# smarty07.net
KiCad netlist of a schematic drawn in EAGLE
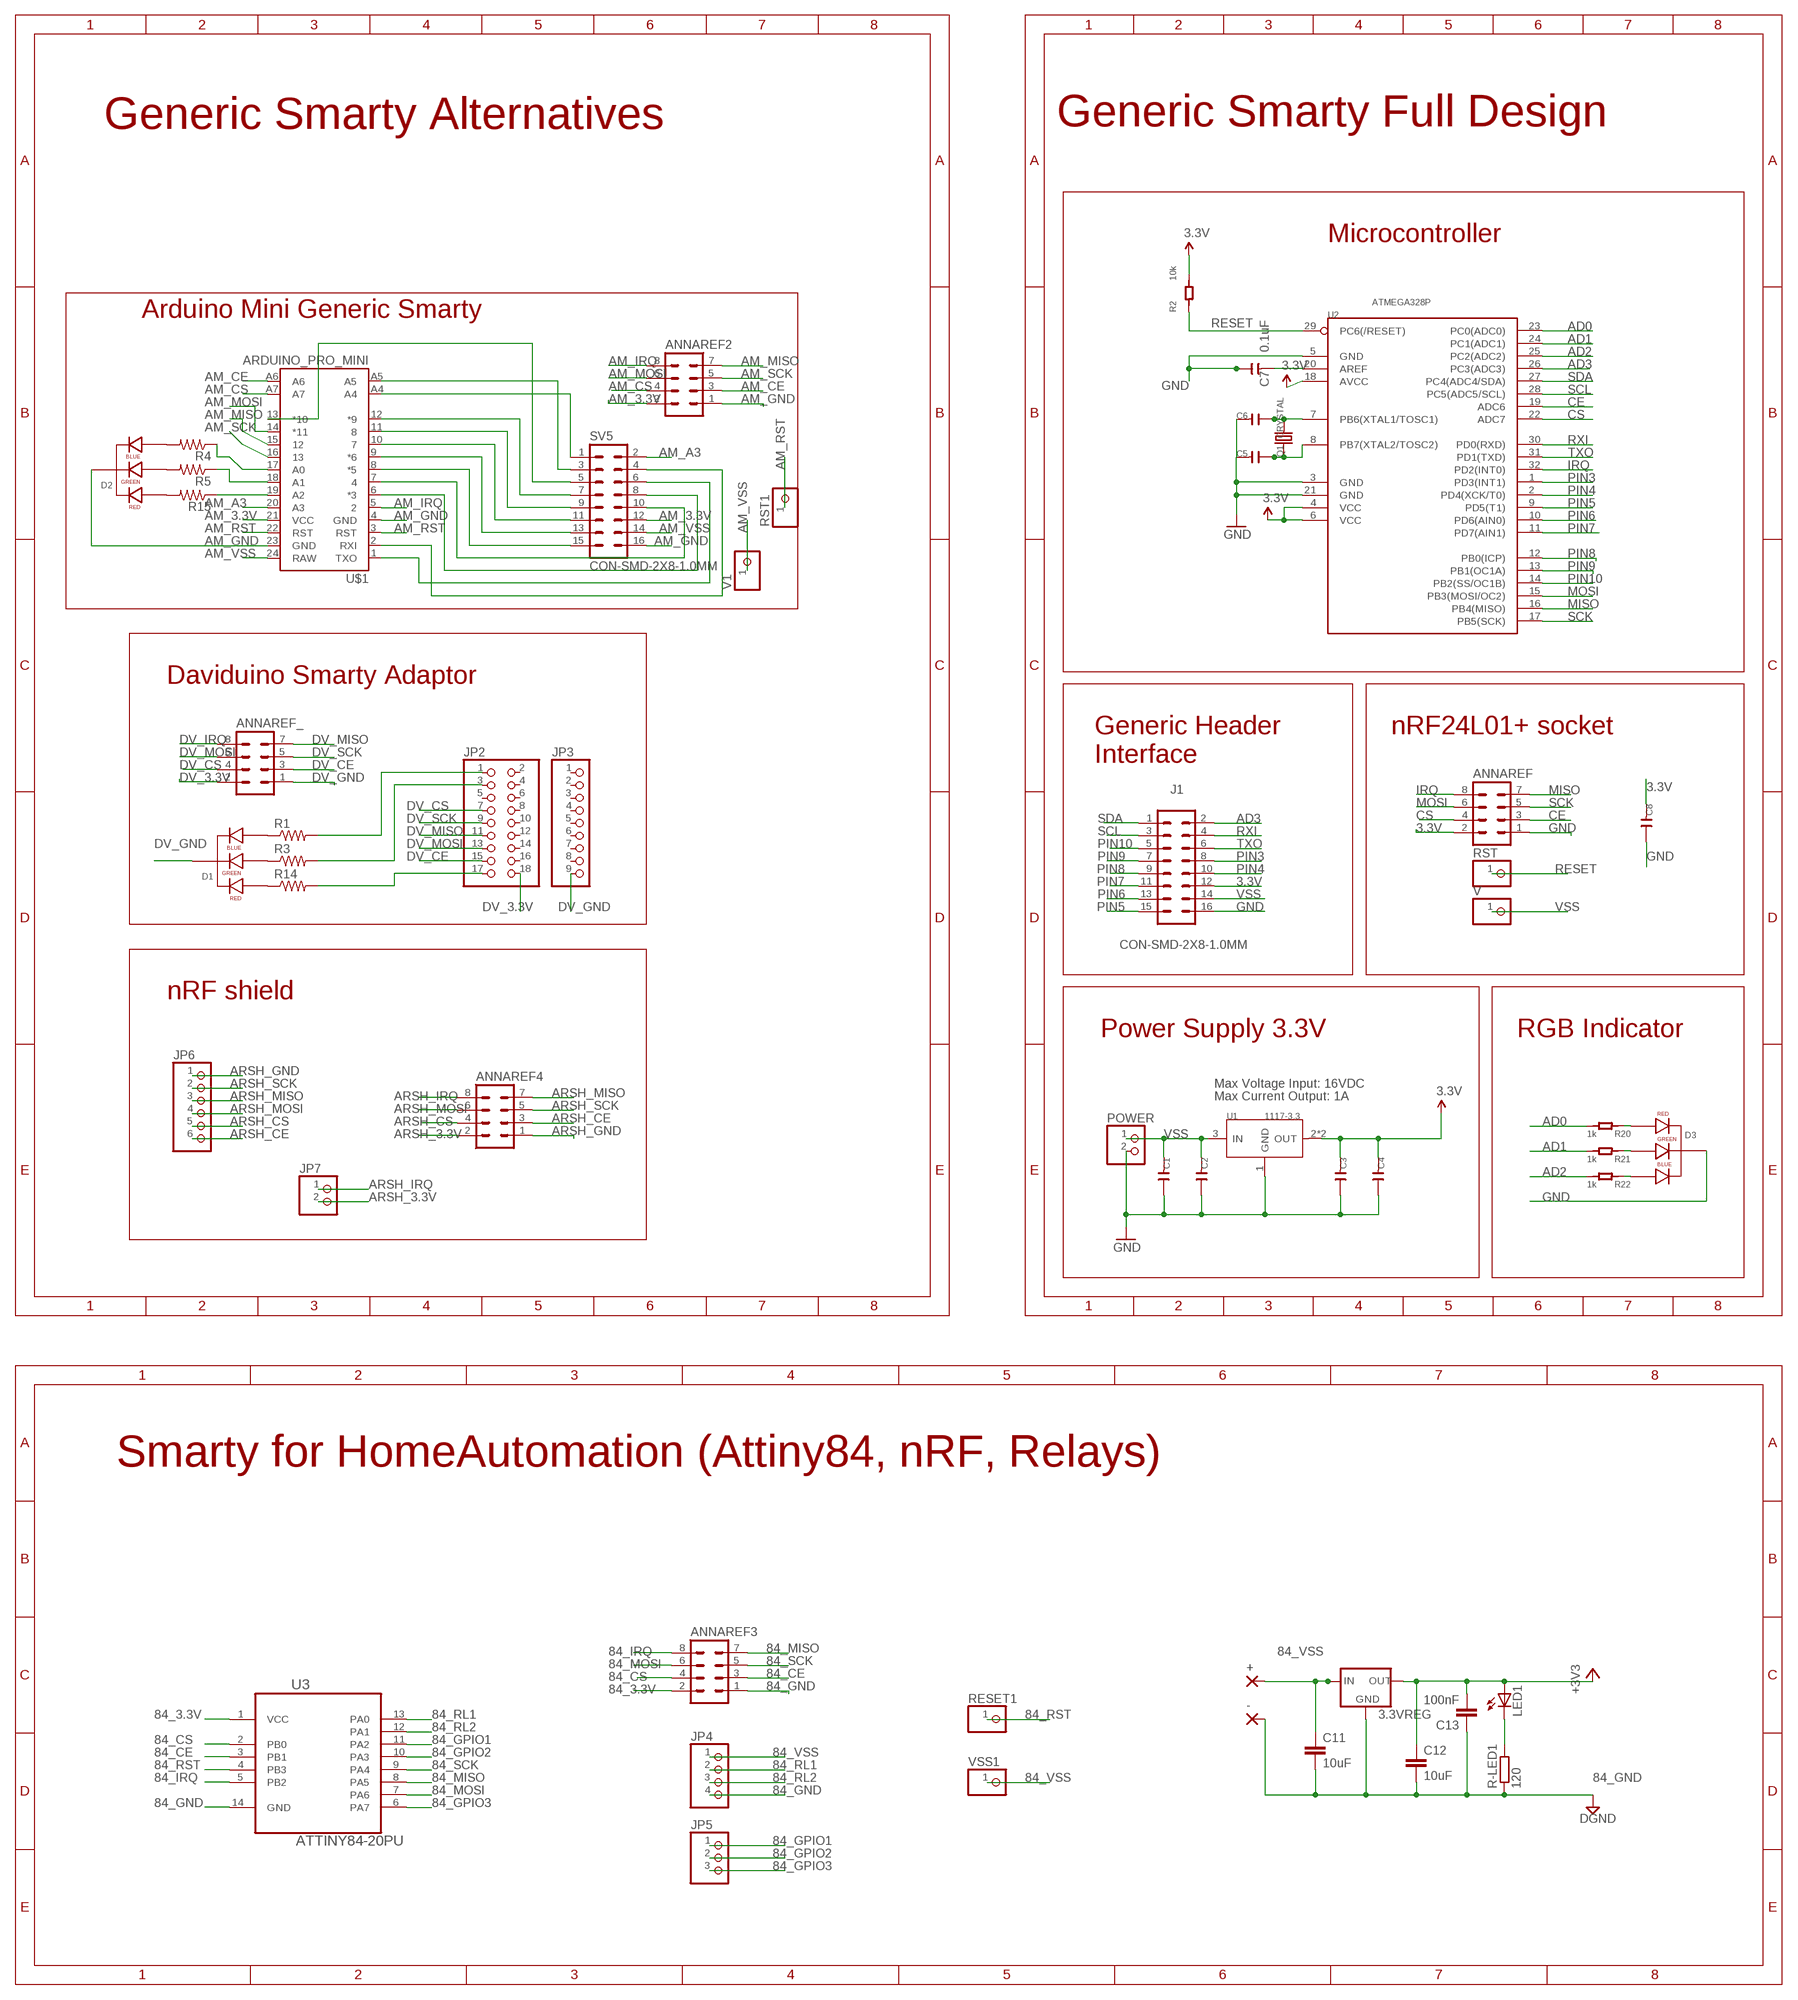
[diagram p0: schematic, sheet 1, part 1 of 2]
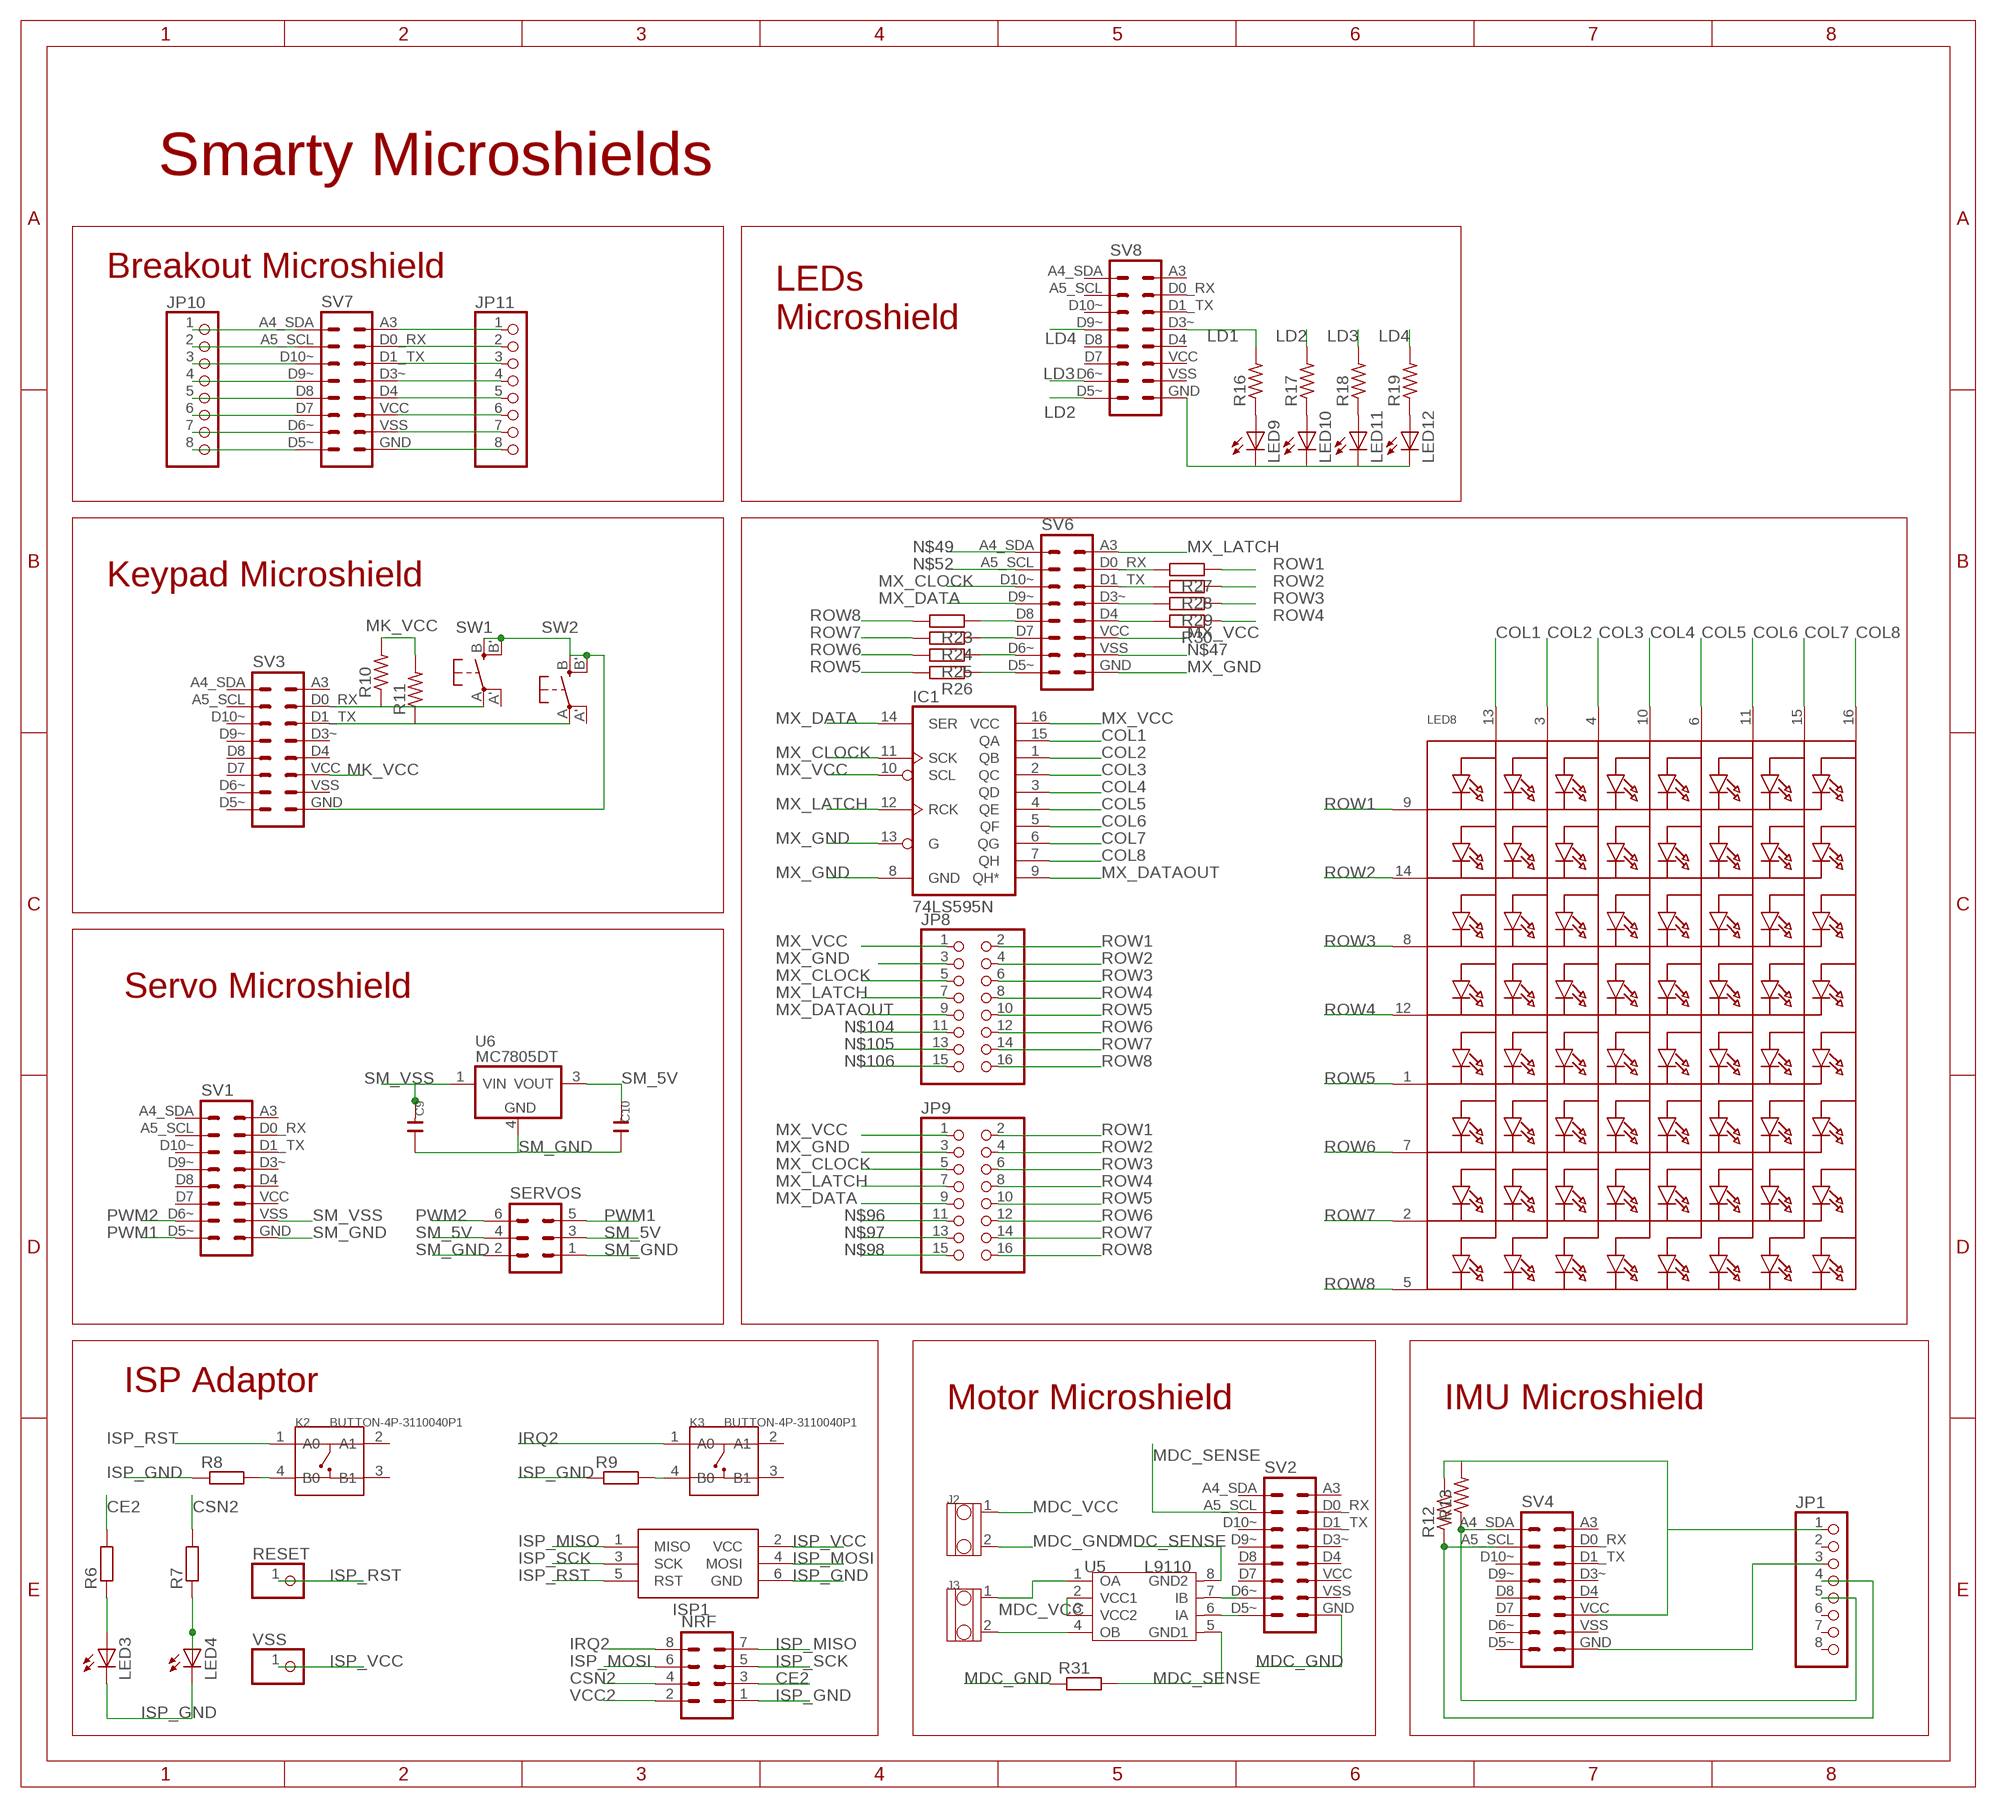
[diagram p1: schematic, sheet 1, part 2 of 2]

(export (version "E")
  (design (tool "Eeschema 10.0.6"))
  (components
    (comp (ref "+")
      (value "2,54/1,1")
      (footprint "eagle-import:2,54_1,1")
      (libsource (lib "eagle-import") (part "2,54/1,1"))
    )
    (comp (ref "-")
      (value "2,54/1,1")
      (footprint "eagle-import:2,54_1,1")
      (libsource (lib "eagle-import") (part "2,54/1,1"))
    )
    (comp (ref "3.3VREG")
      (value "78LXX")
      (footprint "eagle-import:78LXX")
      (libsource (lib "eagle-import") (part "78LXX"))
    )
    (comp (ref "ANNAREF")
      (value "MA04-2")
      (footprint "eagle-import:MA04-2")
      (libsource (lib "eagle-import") (part "MA04-2"))
    )
    (comp (ref "ANNAREF2")
      (value "MA04-2")
      (footprint "eagle-import:MA04-2")
      (libsource (lib "eagle-import") (part "MA04-2"))
    )
    (comp (ref "ANNAREF3")
      (value "MA04-2")
      (footprint "eagle-import:MA04-2")
      (libsource (lib "eagle-import") (part "MA04-2"))
    )
    (comp (ref "ANNAREF4")
      (value "MA04-2")
      (footprint "eagle-import:MA04-2")
      (libsource (lib "eagle-import") (part "MA04-2"))
    )
    (comp (ref "ANNAREF_")
      (value "MA04-2")
      (footprint "eagle-import:MA04-2")
      (libsource (lib "eagle-import") (part "MA04-2"))
    )
    (comp (ref "C1")
      (value "C-0603")
      (footprint "eagle-import:C0603")
      (libsource (lib "eagle-import") (part "C-0603"))
    )
    (comp (ref "C2")
      (value "C-0805")
      (footprint "eagle-import:C0805")
      (libsource (lib "eagle-import") (part "C-0805"))
    )
    (comp (ref "C3")
      (value "C-0603")
      (footprint "eagle-import:C0603")
      (libsource (lib "eagle-import") (part "C-0603"))
    )
    (comp (ref "C4")
      (value "C-0805")
      (footprint "eagle-import:C0805")
      (libsource (lib "eagle-import") (part "C-0805"))
    )
    (comp (ref "C5")
      (value "C-0603")
      (footprint "eagle-import:C0603")
      (libsource (lib "eagle-import") (part "C-0603"))
    )
    (comp (ref "C6")
      (value "C-0603")
      (footprint "eagle-import:C0603")
      (libsource (lib "eagle-import") (part "C-0603"))
    )
    (comp (ref "C7")
      (value "0.1uF")
      (footprint "eagle-import:C0805")
      (libsource (lib "eagle-import") (part "C-0805"))
    )
    (comp (ref "C8")
      (value "C-0805")
      (footprint "eagle-import:C0805")
      (libsource (lib "eagle-import") (part "C-0805"))
    )
    (comp (ref "C9")
      (value "C-0805")
      (footprint "eagle-import:C0805")
      (libsource (lib "eagle-import") (part "C-0805"))
    )
    (comp (ref "C10")
      (value "C-0805")
      (footprint "eagle-import:C0805")
      (libsource (lib "eagle-import") (part "C-0805"))
    )
    (comp (ref "C11")
      (value "10uF")
      (footprint "eagle-import:C025-050X050")
      (libsource (lib "eagle-import") (part "C-EU025-050X050"))
    )
    (comp (ref "C12")
      (value "10uF")
      (footprint "eagle-import:C025-050X050")
      (libsource (lib "eagle-import") (part "C-EU025-050X050"))
    )
    (comp (ref "C13")
      (value "100nF")
      (footprint "eagle-import:C050-024X044")
      (libsource (lib "eagle-import") (part "C-EU050-024X044"))
    )
    (comp (ref "D1")
      (value "LED-RGB-CC-THRUCLEAR")
      (footprint "eagle-import:LED-RGB-THRU")
      (libsource (lib "eagle-import") (part "LED-RGB-CC-THRUCLEAR"))
    )
    (comp (ref "D2")
      (value "LED-RGB-CC-THRUCLEAR")
      (footprint "eagle-import:LED-RGB-THRU")
      (libsource (lib "eagle-import") (part "LED-RGB-CC-THRUCLEAR"))
    )
    (comp (ref "D3")
      (value "LED-RGB-CC-THRUCLEAR")
      (footprint "eagle-import:LED-RGB-THRU")
      (libsource (lib "eagle-import") (part "LED-RGB-CC-THRUCLEAR"))
    )
    (comp (ref "IC1")
      (value "74LS595N")
      (footprint "eagle-import:DIL16")
      (libsource (lib "eagle-import") (part "74595NLS"))
    )
    (comp (ref "ISP1")
      (value "AVRISP-6")
      (footprint "eagle-import:AVRISP")
      (libsource (lib "eagle-import") (part "AVRISP-6"))
    )
    (comp (ref "J1")
      (value "CON-SMD-2X8-1.0MM")
      (footprint "eagle-import:SMRT-FEM-16")
      (libsource (lib "eagle-import") (part "CON-SMD-2X8-1.0MM"))
    )
    (comp (ref "J2")
      (value "SCREW-TERMINAL-2P-3470110P1")
      (footprint "eagle-import:2P-5.0")
      (libsource (lib "eagle-import") (part "SCREW-TERMINAL-2P-3470110P1"))
    )
    (comp (ref "J3")
      (value "SCREW-TERMINAL-2P-3470110P1")
      (footprint "eagle-import:2P-5.0")
      (libsource (lib "eagle-import") (part "SCREW-TERMINAL-2P-3470110P1"))
    )
    (comp (ref "JP1")
      (value "PINHD-1X8BIG")
      (footprint "eagle-import:1X08-BIG")
      (libsource (lib "eagle-import") (part "PINHD-1X8BIG"))
    )
    (comp (ref "JP2")
      (value "PINHD-2X9-BIG")
      (footprint "eagle-import:2X09-BIG")
      (libsource (lib "eagle-import") (part "PINHD-2X9-BIG"))
    )
    (comp (ref "JP3")
      (value "PINHD-1X9")
      (footprint "eagle-import:1X09-BIG")
      (libsource (lib "eagle-import") (part "PINHD-1X9"))
    )
    (comp (ref "JP4")
      (value "PINHD-1X4")
      (footprint "eagle-import:1X04")
      (libsource (lib "eagle-import") (part "PINHD-1X4"))
    )
    (comp (ref "JP5")
      (value "PINHD-1X3")
      (footprint "eagle-import:1X03")
      (libsource (lib "eagle-import") (part "PINHD-1X3"))
    )
    (comp (ref "JP6")
      (value "PINHD-1X6")
      (footprint "eagle-import:1X06")
      (libsource (lib "eagle-import") (part "PINHD-1X6"))
    )
    (comp (ref "JP7")
      (value "PINHD-1X2")
      (footprint "eagle-import:1X02")
      (libsource (lib "eagle-import") (part "PINHD-1X2"))
    )
    (comp (ref "JP8")
      (value "PINHD-2X8")
      (footprint "eagle-import:2X08")
      (libsource (lib "eagle-import") (part "PINHD-2X8"))
    )
    (comp (ref "JP9")
      (value "PINHD-2X8")
      (footprint "eagle-import:2X08")
      (libsource (lib "eagle-import") (part "PINHD-2X8"))
    )
    (comp (ref "JP10")
      (value "PINHD-1X8")
      (footprint "eagle-import:1X08")
      (libsource (lib "eagle-import") (part "PINHD-1X8"))
    )
    (comp (ref "JP11")
      (value "PINHD-1X8")
      (footprint "eagle-import:1X08")
      (libsource (lib "eagle-import") (part "PINHD-1X8"))
    )
    (comp (ref "K2")
      (value "BUTTON-4P-3110040P1")
      (footprint "eagle-import:4P-6.0X6.0X5.0H")
      (libsource (lib "eagle-import") (part "BUTTON-4P-3110040P1"))
    )
    (comp (ref "K3")
      (value "BUTTON-4P-3110040P1")
      (footprint "eagle-import:4P-6.0X6.0X5.0H")
      (libsource (lib "eagle-import") (part "BUTTON-4P-3110040P1"))
    )
    (comp (ref "LED1")
      (value "LED3MM")
      (footprint "eagle-import:LED3MM")
      (libsource (lib "eagle-import") (part "led_LED3MM"))
    )
    (comp (ref "LED3")
      (value "LED3MM")
      (footprint "eagle-import:LED3MM")
      (libsource (lib "eagle-import") (part "led_LED3MM"))
    )
    (comp (ref "LED4")
      (value "LED3MM")
      (footprint "eagle-import:LED3MM")
      (libsource (lib "eagle-import") (part "led_LED3MM"))
    )
    (comp (ref "LED8")
      (value "SEGMENT_8X8_ROWCATHODEM12A881UR")
      (footprint "eagle-import:SEGMENT_BL-M12A881UR")
      (libsource (lib "eagle-import") (part "SEGMENT_8X8_ROWCATHODEM12A881UR"))
    )
    (comp (ref "LED9")
      (value "LEDCHIP-LED0603")
      (footprint "eagle-import:CHIP-LED0603")
      (libsource (lib "eagle-import") (part "LEDCHIP-LED0603"))
    )
    (comp (ref "LED10")
      (value "LEDCHIP-LED0603")
      (footprint "eagle-import:CHIP-LED0603")
      (libsource (lib "eagle-import") (part "LEDCHIP-LED0603"))
    )
    (comp (ref "LED11")
      (value "LEDCHIP-LED0603")
      (footprint "eagle-import:CHIP-LED0603")
      (libsource (lib "eagle-import") (part "LEDCHIP-LED0603"))
    )
    (comp (ref "LED12")
      (value "LEDCHIP-LED0603")
      (footprint "eagle-import:CHIP-LED0603")
      (libsource (lib "eagle-import") (part "LEDCHIP-LED0603"))
    )
    (comp (ref "NRF")
      (value "MA04-2")
      (footprint "eagle-import:MA04-2")
      (libsource (lib "eagle-import") (part "MA04-2"))
    )
    (comp (ref "POWER")
      (value "PINHD-1X2")
      (footprint "eagle-import:1X02")
      (libsource (lib "eagle-import") (part "PINHD-1X2"))
    )
    (comp (ref "Q1")
      (value "CRYSTAL")
      (footprint "eagle-import:2P-SMD-5.0X3.2")
      (libsource (lib "eagle-import") (part "CRYSTAL-0500290P1"))
    )
    (comp (ref "R-LED1")
      (value "120")
      (footprint "eagle-import:0204V")
      (libsource (lib "eagle-import") (part "resistor_R-EU_0204/2V"))
    )
    (comp (ref "R1")
      (value "R-US_0204/2V")
      (footprint "eagle-import:0204V")
      (libsource (lib "eagle-import") (part "resistor_R-US_0204/2V"))
    )
    (comp (ref "R2")
      (value "10k")
      (footprint "eagle-import:R0603")
      (libsource (lib "eagle-import") (part "R-0603"))
    )
    (comp (ref "R3")
      (value "R-US_0204/2V")
      (footprint "eagle-import:0204V")
      (libsource (lib "eagle-import") (part "resistor_R-US_0204/2V"))
    )
    (comp (ref "R4")
      (value "R-US_0207/2V")
      (footprint "eagle-import:0207_2V")
      (libsource (lib "eagle-import") (part "resistor_R-US_0207/2V"))
    )
    (comp (ref "R5")
      (value "R-US_0207/2V")
      (footprint "eagle-import:0207_2V")
      (libsource (lib "eagle-import") (part "resistor_R-US_0207/2V"))
    )
    (comp (ref "R6")
      (value "R-EU_0204/2V")
      (footprint "eagle-import:0204V")
      (libsource (lib "eagle-import") (part "R-EU_0204/2V"))
    )
    (comp (ref "R7")
      (value "R-EU_0204/2V")
      (footprint "eagle-import:0204V")
      (libsource (lib "eagle-import") (part "R-EU_0204/2V"))
    )
    (comp (ref "R8")
      (value "R-EU_0204/2V")
      (footprint "eagle-import:0204V")
      (libsource (lib "eagle-import") (part "R-EU_0204/2V"))
    )
    (comp (ref "R9")
      (value "R-EU_0204/2V")
      (footprint "eagle-import:0204V")
      (libsource (lib "eagle-import") (part "R-EU_0204/2V"))
    )
    (comp (ref "R10")
      (value "R-US_R0603")
      (footprint "eagle-import:R0603")
      (libsource (lib "eagle-import") (part "R-US_R0603"))
    )
    (comp (ref "R11")
      (value "R-US_R0603")
      (footprint "eagle-import:R0603")
      (libsource (lib "eagle-import") (part "R-US_R0603"))
    )
    (comp (ref "R12")
      (value "R-US_R0603")
      (footprint "eagle-import:R0603")
      (libsource (lib "eagle-import") (part "R-US_R0603"))
    )
    (comp (ref "R13")
      (value "R-US_R0603")
      (footprint "eagle-import:R0603")
      (libsource (lib "eagle-import") (part "R-US_R0603"))
    )
    (comp (ref "R14")
      (value "R-US_0204/2V")
      (footprint "eagle-import:0204V")
      (libsource (lib "eagle-import") (part "resistor_R-US_0204/2V"))
    )
    (comp (ref "R15")
      (value "R-US_0207/2V")
      (footprint "eagle-import:0207_2V")
      (libsource (lib "eagle-import") (part "resistor_R-US_0207/2V"))
    )
    (comp (ref "R16")
      (value "R-US_R0603")
      (footprint "eagle-import:R0603")
      (libsource (lib "eagle-import") (part "R-US_R0603"))
    )
    (comp (ref "R17")
      (value "R-US_R0603")
      (footprint "eagle-import:R0603")
      (libsource (lib "eagle-import") (part "R-US_R0603"))
    )
    (comp (ref "R18")
      (value "R-US_R0603")
      (footprint "eagle-import:R0603")
      (libsource (lib "eagle-import") (part "R-US_R0603"))
    )
    (comp (ref "R19")
      (value "R-US_R0603")
      (footprint "eagle-import:R0603")
      (libsource (lib "eagle-import") (part "R-US_R0603"))
    )
    (comp (ref "R20")
      (value "1k")
      (footprint "eagle-import:R0603")
      (libsource (lib "eagle-import") (part "R-0603"))
    )
    (comp (ref "R21")
      (value "1k")
      (footprint "eagle-import:R0603")
      (libsource (lib "eagle-import") (part "R-0603"))
    )
    (comp (ref "R22")
      (value "1k")
      (footprint "eagle-import:R0603")
      (libsource (lib "eagle-import") (part "R-0603"))
    )
    (comp (ref "R23")
      (value "R-EU_R0603")
      (footprint "eagle-import:R0603")
      (libsource (lib "eagle-import") (part "resistor_R-EU_R0603"))
    )
    (comp (ref "R24")
      (value "R-EU_R0603")
      (footprint "eagle-import:R0603")
      (libsource (lib "eagle-import") (part "resistor_R-EU_R0603"))
    )
    (comp (ref "R25")
      (value "R-EU_R0603")
      (footprint "eagle-import:R0603")
      (libsource (lib "eagle-import") (part "resistor_R-EU_R0603"))
    )
    (comp (ref "R26")
      (value "R-EU_R0603")
      (footprint "eagle-import:R0603")
      (libsource (lib "eagle-import") (part "resistor_R-EU_R0603"))
    )
    (comp (ref "R27")
      (value "R-EU_R0603")
      (footprint "eagle-import:R0603")
      (libsource (lib "eagle-import") (part "resistor_R-EU_R0603"))
    )
    (comp (ref "R28")
      (value "R-EU_R0603")
      (footprint "eagle-import:R0603")
      (libsource (lib "eagle-import") (part "resistor_R-EU_R0603"))
    )
    (comp (ref "R29")
      (value "R-EU_R0603")
      (footprint "eagle-import:R0603")
      (libsource (lib "eagle-import") (part "resistor_R-EU_R0603"))
    )
    (comp (ref "R30")
      (value "R-EU_R0603")
      (footprint "eagle-import:R0603")
      (libsource (lib "eagle-import") (part "resistor_R-EU_R0603"))
    )
    (comp (ref "R31")
      (value "R-EU_R1206")
      (footprint "eagle-import:R1206")
      (libsource (lib "eagle-import") (part "resistor_R-EU_R1206"))
    )
    (comp (ref "RESET")
      (value "PINHD-1X1")
      (footprint "eagle-import:1X01")
      (libsource (lib "eagle-import") (part "PINHD-1X1"))
    )
    (comp (ref "RESET1")
      (value "PINHD-1X1")
      (footprint "eagle-import:1X01")
      (libsource (lib "eagle-import") (part "PINHD-1X1"))
    )
    (comp (ref "RST")
      (value "PINHD-1X1")
      (footprint "eagle-import:1X01")
      (libsource (lib "eagle-import") (part "PINHD-1X1"))
    )
    (comp (ref "RST1")
      (value "PINHD-1X1")
      (footprint "eagle-import:1X01")
      (libsource (lib "eagle-import") (part "PINHD-1X1"))
    )
    (comp (ref "SERVOS")
      (value "MA03-2")
      (footprint "eagle-import:MA03-2")
      (libsource (lib "eagle-import") (part "MA03-2"))
    )
    (comp (ref "SV1")
      (value "MA08-2")
      (footprint "eagle-import:MA08-2")
      (libsource (lib "eagle-import") (part "MA08-2"))
    )
    (comp (ref "SV2")
      (value "MA08-2")
      (footprint "eagle-import:MA08-2")
      (libsource (lib "eagle-import") (part "MA08-2"))
    )
    (comp (ref "SV3")
      (value "MA08-2")
      (footprint "eagle-import:MA08-2")
      (libsource (lib "eagle-import") (part "MA08-2"))
    )
    (comp (ref "SV4")
      (value "MA08-2")
      (footprint "eagle-import:MA08-2")
      (libsource (lib "eagle-import") (part "MA08-2"))
    )
    (comp (ref "SV5")
      (value "CON-SMD-2X8-1.0MM")
      (footprint "eagle-import:SMRT-FEM-16")
      (libsource (lib "eagle-import") (part "CON-SMD-2X8-1.0MM"))
    )
    (comp (ref "SV6")
      (value "MA08-2")
      (footprint "eagle-import:MA08-2")
      (libsource (lib "eagle-import") (part "MA08-2"))
    )
    (comp (ref "SV7")
      (value "MA08-2")
      (footprint "eagle-import:MA08-2")
      (libsource (lib "eagle-import") (part "MA08-2"))
    )
    (comp (ref "SV8")
      (value "MA08-2")
      (footprint "eagle-import:MA08-2")
      (libsource (lib "eagle-import") (part "MA08-2"))
    )
    (comp (ref "SW1")
      (value "SPST_TACT-EVQQ2")
      (footprint "eagle-import:EVQ-Q2")
      (libsource (lib "eagle-import") (part "SPST_TACT-EVQQ2"))
    )
    (comp (ref "SW2")
      (value "SPST_TACT-EVQQ2")
      (footprint "eagle-import:EVQ-Q2")
      (libsource (lib "eagle-import") (part "SPST_TACT-EVQQ2"))
    )
    (comp (ref "U$1")
      (value "ARDUINO_PRO_MINI")
      (footprint "eagle-import:ARDUINO_PRO_MINI")
      (libsource (lib "eagle-import") (part "ARDUINO_PRO_MINI"))
    )
    (comp (ref "U1")
      (value "1117-3.3")
      (footprint "eagle-import:SOT89")
      (libsource (lib "eagle-import") (part "CJ1117-3.3-1310120P1"))
    )
    (comp (ref "U2")
      (value "ATMEGA328P")
      (footprint "eagle-import:TQFP32")
      (libsource (lib "eagle-import") (part "ATMEGA328P-AU-1030060P1"))
    )
    (comp (ref "U3")
      (value "ATTINY84-20PU")
      (footprint "eagle-import:DIP254P762X533-14")
      (libsource (lib "eagle-import") (part "ATTINY84-20PU"))
    )
    (comp (ref "U5")
      (value "L9110")
      (footprint "eagle-import:SOIC8")
      (libsource (lib "eagle-import") (part "L9110-SOIC8"))
    )
    (comp (ref "U6")
      (value "MC7805DT")
      (footprint "eagle-import:DPAK-3")
      (libsource (lib "eagle-import") (part "MC78DT05"))
    )
    (comp (ref "V")
      (value "PINHD-1X1")
      (footprint "eagle-import:1X01")
      (libsource (lib "eagle-import") (part "PINHD-1X1"))
    )
    (comp (ref "V1")
      (value "PINHD-1X1")
      (footprint "eagle-import:1X01")
      (libsource (lib "eagle-import") (part "PINHD-1X1"))
    )
    (comp (ref "VSS")
      (value "PINHD-1X1")
      (footprint "eagle-import:1X01")
      (libsource (lib "eagle-import") (part "PINHD-1X1"))
    )
    (comp (ref "VSS1")
      (value "PINHD-1X1")
      (footprint "eagle-import:1X01")
      (libsource (lib "eagle-import") (part "PINHD-1X1"))
    )
  )
  (nets
    (net (code "1") (name "+3V3") (class "Default")
      (node (ref "3.3VREG") (pin "OUT") (pinfunction "OUT_OUT") (pintype "passive"))
      (node (ref "C12") (pin "1") (pinfunction "1_1") (pintype "passive"))
      (node (ref "C13") (pin "2") (pinfunction "2_2") (pintype "passive"))
      (node (ref "LED1") (pin "A") (pinfunction "A_A") (pintype "passive"))
    )
    (net (code "2") (name "/84_3.3V") (class "Default")
      (node (ref "ANNAREF3") (pin "2") (pinfunction "2_2") (pintype "passive"))
      (node (ref "U3") (pin "1") (pinfunction "VCC_1") (pintype "power_in"))
    )
    (net (code "3") (name "/84_CE") (class "Default")
      (node (ref "ANNAREF3") (pin "3") (pinfunction "3_3") (pintype "passive"))
      (node (ref "U3") (pin "3") (pinfunction "PB1_3") (pintype "bidirectional"))
    )
    (net (code "4") (name "/84_CS") (class "Default")
      (node (ref "ANNAREF3") (pin "4") (pinfunction "4_4") (pintype "passive"))
      (node (ref "U3") (pin "2") (pinfunction "PB0_2") (pintype "bidirectional"))
    )
    (net (code "5") (name "/84_GPIO1") (class "Default")
      (node (ref "JP5") (pin "1") (pinfunction "1_1") (pintype "passive"))
      (node (ref "U3") (pin "11") (pinfunction "PA2_11") (pintype "bidirectional"))
    )
    (net (code "6") (name "/84_GPIO2") (class "Default")
      (node (ref "JP5") (pin "2") (pinfunction "2_2") (pintype "passive"))
      (node (ref "U3") (pin "10") (pinfunction "PA3_10") (pintype "bidirectional"))
    )
    (net (code "7") (name "/84_GPIO3") (class "Default")
      (node (ref "JP5") (pin "3") (pinfunction "3_3") (pintype "passive"))
      (node (ref "U3") (pin "6") (pinfunction "PA7_6") (pintype "bidirectional"))
    )
    (net (code "8") (name "/84_IRQ") (class "Default")
      (node (ref "ANNAREF3") (pin "8") (pinfunction "8_8") (pintype "passive"))
      (node (ref "U3") (pin "5") (pinfunction "PB2_5") (pintype "bidirectional"))
    )
    (net (code "9") (name "/84_MISO") (class "Default")
      (node (ref "ANNAREF3") (pin "7") (pinfunction "7_7") (pintype "passive"))
      (node (ref "U3") (pin "8") (pinfunction "PA5_8") (pintype "bidirectional"))
    )
    (net (code "10") (name "/84_MOSI") (class "Default")
      (node (ref "ANNAREF3") (pin "6") (pinfunction "6_6") (pintype "passive"))
      (node (ref "U3") (pin "7") (pinfunction "PA6_7") (pintype "bidirectional"))
    )
    (net (code "11") (name "/84_RL1") (class "Default")
      (node (ref "JP4") (pin "2") (pinfunction "2_2") (pintype "passive"))
      (node (ref "U3") (pin "13") (pinfunction "PA0_13") (pintype "bidirectional"))
    )
    (net (code "12") (name "/84_RL2") (class "Default")
      (node (ref "JP4") (pin "3") (pinfunction "3_3") (pintype "passive"))
      (node (ref "U3") (pin "12") (pinfunction "PA1_12") (pintype "bidirectional"))
    )
    (net (code "13") (name "/84_RST") (class "Default")
      (node (ref "RESET1") (pin "1") (pinfunction "1_1") (pintype "passive"))
      (node (ref "U3") (pin "4") (pinfunction "PB3_4") (pintype "bidirectional"))
    )
    (net (code "14") (name "/84_SCK") (class "Default")
      (node (ref "ANNAREF3") (pin "5") (pinfunction "5_5") (pintype "passive"))
      (node (ref "U3") (pin "9") (pinfunction "PA4_9") (pintype "bidirectional"))
    )
    (net (code "15") (name "/84_VSS") (class "Default")
      (node (ref "+") (pin "1") (pinfunction "P_1") (pintype "passive"))
      (node (ref "3.3VREG") (pin "IN") (pinfunction "IN_IN") (pintype "input"))
      (node (ref "C11") (pin "1") (pinfunction "1_1") (pintype "passive"))
      (node (ref "JP4") (pin "1") (pinfunction "1_1") (pintype "passive"))
      (node (ref "VSS1") (pin "1") (pinfunction "1_1") (pintype "passive"))
    )
    (net (code "16") (name "/AD0") (class "Default")
      (node (ref "R20") (pin "2") (pinfunction "2_2") (pintype "bidirectional"))
      (node (ref "U2") (pin "23") (pinfunction "PC0(ADC0)_23") (pintype "bidirectional"))
    )
    (net (code "17") (name "/AD1") (class "Default")
      (node (ref "R21") (pin "2") (pinfunction "2_2") (pintype "bidirectional"))
      (node (ref "U2") (pin "24") (pinfunction "PC1(ADC1)_24") (pintype "bidirectional"))
    )
    (net (code "18") (name "/AD2") (class "Default")
      (node (ref "R22") (pin "2") (pinfunction "2_2") (pintype "bidirectional"))
      (node (ref "U2") (pin "25") (pinfunction "PC2(ADC2)_25") (pintype "bidirectional"))
    )
    (net (code "19") (name "/AD3") (class "Default")
      (node (ref "J1") (pin "2") (pinfunction "A3_2") (pintype "passive"))
      (node (ref "U2") (pin "26") (pinfunction "PC3(ADC3)_26") (pintype "bidirectional"))
    )
    (net (code "20") (name "/AM_3.3V") (class "Default")
      (node (ref "ANNAREF2") (pin "2") (pinfunction "2_2") (pintype "passive"))
      (node (ref "SV5") (pin "12") (pinfunction "VCC_12") (pintype "passive"))
      (node (ref "U$1") (pin "21") (pinfunction "VCC_21") (pintype "bidirectional"))
    )
    (net (code "21") (name "/AM_A3") (class "Default")
      (node (ref "SV5") (pin "2") (pinfunction "A3_2") (pintype "passive"))
      (node (ref "U$1") (pin "20") (pinfunction "A3_20") (pintype "bidirectional"))
    )
    (net (code "22") (name "/AM_CE") (class "Default")
      (node (ref "ANNAREF2") (pin "3") (pinfunction "3_3") (pintype "passive"))
      (node (ref "U$1") (pin "A6") (pinfunction "A6_A6") (pintype "bidirectional"))
    )
    (net (code "23") (name "/AM_CS") (class "Default")
      (node (ref "ANNAREF2") (pin "4") (pinfunction "4_4") (pintype "passive"))
      (node (ref "U$1") (pin "A7") (pinfunction "A7_A7") (pintype "bidirectional"))
    )
    (net (code "24") (name "/AM_GND") (class "Default")
      (node (ref "ANNAREF2") (pin "1") (pinfunction "1_1") (pintype "passive"))
      (node (ref "D2") (pin "2") (pinfunction "CATHODE_2") (pintype "bidirectional"))
      (node (ref "SV5") (pin "16") (pinfunction "GND_16") (pintype "passive"))
      (node (ref "U$1") (pin "23") (pinfunction "GND_23") (pintype "bidirectional"))
      (node (ref "U$1") (pin "4") (pinfunction "GND_4") (pintype "bidirectional"))
    )
    (net (code "25") (name "/AM_IRQ") (class "Default")
      (node (ref "ANNAREF2") (pin "8") (pinfunction "8_8") (pintype "passive"))
      (node (ref "U$1") (pin "5") (pinfunction "2_5") (pintype "bidirectional"))
    )
    (net (code "26") (name "/AM_MISO") (class "Default")
      (node (ref "ANNAREF2") (pin "7") (pinfunction "7_7") (pintype "passive"))
      (node (ref "U$1") (pin "15") (pinfunction "12_15") (pintype "bidirectional"))
    )
    (net (code "27") (name "/AM_MOSI") (class "Default")
      (node (ref "ANNAREF2") (pin "6") (pinfunction "6_6") (pintype "passive"))
      (node (ref "U$1") (pin "14") (pinfunction "*11_14") (pintype "bidirectional"))
    )
    (net (code "28") (name "/AM_RST") (class "Default")
      (node (ref "RST1") (pin "1") (pinfunction "1_1") (pintype "passive"))
      (node (ref "U$1") (pin "22") (pinfunction "RST_22") (pintype "bidirectional"))
      (node (ref "U$1") (pin "3") (pinfunction "RST_3") (pintype "bidirectional"))
    )
    (net (code "29") (name "/AM_SCK") (class "Default")
      (node (ref "ANNAREF2") (pin "5") (pinfunction "5_5") (pintype "passive"))
      (node (ref "U$1") (pin "16") (pinfunction "13_16") (pintype "bidirectional"))
    )
    (net (code "30") (name "/AM_VSS") (class "Default")
      (node (ref "SV5") (pin "14") (pinfunction "VSS_14") (pintype "passive"))
      (node (ref "U$1") (pin "24") (pinfunction "RAW_24") (pintype "bidirectional"))
      (node (ref "V1") (pin "1") (pinfunction "1_1") (pintype "passive"))
    )
    (net (code "31") (name "/ARSH_3.3V") (class "Default")
      (node (ref "ANNAREF4") (pin "2") (pinfunction "2_2") (pintype "passive"))
      (node (ref "JP7") (pin "2") (pinfunction "2_2") (pintype "passive"))
    )
    (net (code "32") (name "/ARSH_CE") (class "Default")
      (node (ref "ANNAREF4") (pin "3") (pinfunction "3_3") (pintype "passive"))
      (node (ref "JP6") (pin "6") (pinfunction "6_6") (pintype "passive"))
    )
    (net (code "33") (name "/ARSH_CS") (class "Default")
      (node (ref "ANNAREF4") (pin "4") (pinfunction "4_4") (pintype "passive"))
      (node (ref "JP6") (pin "5") (pinfunction "5_5") (pintype "passive"))
    )
    (net (code "34") (name "/ARSH_GND") (class "Default")
      (node (ref "ANNAREF4") (pin "1") (pinfunction "1_1") (pintype "passive"))
      (node (ref "JP6") (pin "1") (pinfunction "1_1") (pintype "passive"))
    )
    (net (code "35") (name "/ARSH_IRQ") (class "Default")
      (node (ref "ANNAREF4") (pin "8") (pinfunction "8_8") (pintype "passive"))
      (node (ref "JP7") (pin "1") (pinfunction "1_1") (pintype "passive"))
    )
    (net (code "36") (name "/ARSH_MISO") (class "Default")
      (node (ref "ANNAREF4") (pin "7") (pinfunction "7_7") (pintype "passive"))
      (node (ref "JP6") (pin "3") (pinfunction "3_3") (pintype "passive"))
    )
    (net (code "37") (name "/ARSH_MOSI") (class "Default")
      (node (ref "ANNAREF4") (pin "6") (pinfunction "6_6") (pintype "passive"))
      (node (ref "JP6") (pin "4") (pinfunction "4_4") (pintype "passive"))
    )
    (net (code "38") (name "/ARSH_SCK") (class "Default")
      (node (ref "ANNAREF4") (pin "5") (pinfunction "5_5") (pintype "passive"))
      (node (ref "JP6") (pin "2") (pinfunction "2_2") (pintype "passive"))
    )
    (net (code "39") (name "/CE") (class "Default")
      (node (ref "ANNAREF") (pin "3") (pinfunction "3_3") (pintype "passive"))
      (node (ref "U2") (pin "19") (pinfunction "ADC6_19") (pintype "bidirectional"))
    )
    (net (code "40") (name "/CE2") (class "Default")
      (node (ref "NRF") (pin "3") (pinfunction "3_3") (pintype "passive"))
      (node (ref "R6") (pin "2") (pinfunction "2_2") (pintype "passive"))
    )
    (net (code "41") (name "/COL1") (class "Default")
      (node (ref "IC1") (pin "15") (pinfunction "QA_15") (pintype "tri_state"))
      (node (ref "LED8") (pin "13") (pinfunction "A1_13") (pintype "bidirectional"))
    )
    (net (code "42") (name "/COL2") (class "Default")
      (node (ref "IC1") (pin "1") (pinfunction "QB_1") (pintype "tri_state"))
      (node (ref "LED8") (pin "3") (pinfunction "A2_3") (pintype "bidirectional"))
    )
    (net (code "43") (name "/COL3") (class "Default")
      (node (ref "IC1") (pin "2") (pinfunction "QC_2") (pintype "tri_state"))
      (node (ref "LED8") (pin "4") (pinfunction "A3_4") (pintype "bidirectional"))
    )
    (net (code "44") (name "/COL4") (class "Default")
      (node (ref "IC1") (pin "3") (pinfunction "QD_3") (pintype "tri_state"))
      (node (ref "LED8") (pin "10") (pinfunction "A4_10") (pintype "bidirectional"))
    )
    (net (code "45") (name "/COL5") (class "Default")
      (node (ref "IC1") (pin "4") (pinfunction "QE_4") (pintype "tri_state"))
      (node (ref "LED8") (pin "6") (pinfunction "A5_6") (pintype "bidirectional"))
    )
    (net (code "46") (name "/COL6") (class "Default")
      (node (ref "IC1") (pin "5") (pinfunction "QF_5") (pintype "tri_state"))
      (node (ref "LED8") (pin "11") (pinfunction "A6_11") (pintype "bidirectional"))
    )
    (net (code "47") (name "/COL7") (class "Default")
      (node (ref "IC1") (pin "6") (pinfunction "QG_6") (pintype "tri_state"))
      (node (ref "LED8") (pin "15") (pinfunction "A7_15") (pintype "bidirectional"))
    )
    (net (code "48") (name "/COL8") (class "Default")
      (node (ref "IC1") (pin "7") (pinfunction "QH_7") (pintype "tri_state"))
      (node (ref "LED8") (pin "16") (pinfunction "A8_16") (pintype "bidirectional"))
    )
    (net (code "49") (name "/CS") (class "Default")
      (node (ref "ANNAREF") (pin "4") (pinfunction "4_4") (pintype "passive"))
      (node (ref "U2") (pin "22") (pinfunction "ADC7_22") (pintype "bidirectional"))
    )
    (net (code "50") (name "/CSN2") (class "Default")
      (node (ref "NRF") (pin "4") (pinfunction "4_4") (pintype "passive"))
      (node (ref "R7") (pin "2") (pinfunction "2_2") (pintype "passive"))
    )
    (net (code "51") (name "/DV_3.3V") (class "Default")
      (node (ref "ANNAREF_") (pin "2") (pinfunction "2_2") (pintype "passive"))
      (node (ref "JP2") (pin "18") (pinfunction "18_18") (pintype "passive"))
    )
    (net (code "52") (name "/DV_CE") (class "Default")
      (node (ref "ANNAREF_") (pin "3") (pinfunction "3_3") (pintype "passive"))
      (node (ref "JP2") (pin "15") (pinfunction "15_15") (pintype "passive"))
    )
    (net (code "53") (name "/DV_CS") (class "Default")
      (node (ref "ANNAREF_") (pin "4") (pinfunction "4_4") (pintype "passive"))
      (node (ref "JP2") (pin "7") (pinfunction "7_7") (pintype "passive"))
    )
    (net (code "54") (name "/DV_GND") (class "Default")
      (node (ref "ANNAREF_") (pin "1") (pinfunction "1_1") (pintype "passive"))
      (node (ref "D1") (pin "2") (pinfunction "CATHODE_2") (pintype "bidirectional"))
      (node (ref "JP3") (pin "9") (pinfunction "9_9") (pintype "passive"))
    )
    (net (code "55") (name "/DV_IRQ") (class "Default")
      (node (ref "ANNAREF_") (pin "8") (pinfunction "8_8") (pintype "passive"))
    )
    (net (code "56") (name "/DV_MISO") (class "Default")
      (node (ref "ANNAREF_") (pin "7") (pinfunction "7_7") (pintype "passive"))
      (node (ref "JP2") (pin "11") (pinfunction "11_11") (pintype "passive"))
    )
    (net (code "57") (name "/DV_MOSI") (class "Default")
      (node (ref "ANNAREF_") (pin "6") (pinfunction "6_6") (pintype "passive"))
      (node (ref "JP2") (pin "13") (pinfunction "13_13") (pintype "passive"))
    )
    (net (code "58") (name "/DV_SCK") (class "Default")
      (node (ref "ANNAREF_") (pin "5") (pinfunction "5_5") (pintype "passive"))
      (node (ref "JP2") (pin "9") (pinfunction "9_9") (pintype "passive"))
    )
    (net (code "59") (name "/IRQ") (class "Default")
      (node (ref "ANNAREF") (pin "8") (pinfunction "8_8") (pintype "passive"))
      (node (ref "U2") (pin "32") (pinfunction "PD2(INT0)_32") (pintype "bidirectional"))
    )
    (net (code "60") (name "/IRQ2") (class "Default")
      (node (ref "K3") (pin "1") (pinfunction "A0_1") (pintype "bidirectional"))
      (node (ref "NRF") (pin "8") (pinfunction "8_8") (pintype "passive"))
    )
    (net (code "61") (name "/ISP_GND") (class "Default")
      (node (ref "ISP1") (pin "6") (pinfunction "GND_6") (pintype "power_in"))
      (node (ref "LED3") (pin "K") (pinfunction "C_K") (pintype "passive"))
      (node (ref "LED4") (pin "K") (pinfunction "C_K") (pintype "passive"))
      (node (ref "NRF") (pin "1") (pinfunction "1_1") (pintype "passive"))
      (node (ref "R8") (pin "1") (pinfunction "1_1") (pintype "passive"))
      (node (ref "R9") (pin "1") (pinfunction "1_1") (pintype "passive"))
    )
    (net (code "62") (name "/ISP_MISO") (class "Default")
      (node (ref "ISP1") (pin "1") (pinfunction "MISO_1") (pintype "input"))
      (node (ref "NRF") (pin "7") (pinfunction "7_7") (pintype "passive"))
    )
    (net (code "63") (name "/ISP_MOSI") (class "Default")
      (node (ref "ISP1") (pin "4") (pinfunction "MOSI_4") (pintype "output"))
      (node (ref "NRF") (pin "6") (pinfunction "6_6") (pintype "passive"))
    )
    (net (code "64") (name "/ISP_RST") (class "Default")
      (node (ref "ISP1") (pin "5") (pinfunction "RST_5") (pintype "output"))
      (node (ref "K2") (pin "1") (pinfunction "A0_1") (pintype "bidirectional"))
      (node (ref "RESET") (pin "1") (pinfunction "1_1") (pintype "passive"))
    )
    (net (code "65") (name "/ISP_SCK") (class "Default")
      (node (ref "ISP1") (pin "3") (pinfunction "SCK_3") (pintype "output"))
      (node (ref "NRF") (pin "5") (pinfunction "5_5") (pintype "passive"))
    )
    (net (code "66") (name "/ISP_VCC") (class "Default")
      (node (ref "ISP1") (pin "2") (pinfunction "VCC_2") (pintype "power_in"))
      (node (ref "VSS") (pin "1") (pinfunction "1_1") (pintype "passive"))
    )
    (net (code "67") (name "/LD1") (class "Default")
      (node (ref "R16") (pin "2") (pinfunction "2_2") (pintype "passive"))
      (node (ref "SV8") (pin "D3~") (pinfunction "D3~{}_D3~") (pintype "passive"))
    )
    (net (code "68") (name "/LD2") (class "Default")
      (node (ref "R17") (pin "2") (pinfunction "2_2") (pintype "passive"))
      (node (ref "SV8") (pin "D5~") (pinfunction "D5~{}_D5~") (pintype "passive"))
    )
    (net (code "69") (name "/LD3") (class "Default")
      (node (ref "R18") (pin "2") (pinfunction "2_2") (pintype "passive"))
      (node (ref "SV8") (pin "D6~") (pinfunction "D6~{}_D6~") (pintype "passive"))
    )
    (net (code "70") (name "/LD4") (class "Default")
      (node (ref "R19") (pin "2") (pinfunction "2_2") (pintype "passive"))
      (node (ref "SV8") (pin "D9~") (pinfunction "D9~{}_D9~") (pintype "passive"))
    )
    (net (code "71") (name "/MDC_GND") (class "Default")
      (node (ref "J2") (pin "2") (pinfunction "2_2") (pintype "bidirectional"))
      (node (ref "R31") (pin "1") (pinfunction "1_1") (pintype "passive"))
      (node (ref "SV2") (pin "GND") (pinfunction "GND_GND") (pintype "passive"))
    )
    (net (code "72") (name "/MDC_SENSE") (class "Default")
      (node (ref "R31") (pin "2") (pinfunction "2_2") (pintype "passive"))
      (node (ref "SV2") (pin "A5_SCL") (pinfunction "A5_SCL_A5_SCL") (pintype "passive"))
      (node (ref "U5") (pin "5") (pinfunction "GND1_5") (pintype "power_in"))
      (node (ref "U5") (pin "8") (pinfunction "GND2_8") (pintype "power_in"))
    )
    (net (code "73") (name "/MDC_VCC") (class "Default")
      (node (ref "J2") (pin "1") (pinfunction "1_1") (pintype "bidirectional"))
      (node (ref "U5") (pin "2") (pinfunction "VCC1_2") (pintype "power_in"))
      (node (ref "U5") (pin "3") (pinfunction "VCC2_3") (pintype "output"))
    )
    (net (code "74") (name "/MISO") (class "Default")
      (node (ref "ANNAREF") (pin "7") (pinfunction "7_7") (pintype "passive"))
      (node (ref "U2") (pin "16") (pinfunction "PB4(MISO)_16") (pintype "bidirectional"))
    )
    (net (code "75") (name "/MK_VCC") (class "Default")
      (node (ref "R10") (pin "2") (pinfunction "2_2") (pintype "passive"))
      (node (ref "R11") (pin "2") (pinfunction "2_2") (pintype "passive"))
      (node (ref "SV3") (pin "VCC") (pinfunction "VCC_VCC") (pintype "passive"))
    )
    (net (code "76") (name "/MOSI") (class "Default")
      (node (ref "ANNAREF") (pin "6") (pinfunction "6_6") (pintype "passive"))
      (node (ref "U2") (pin "15") (pinfunction "PB3(MOSI/OC2)_15") (pintype "bidirectional"))
    )
    (net (code "77") (name "/MX_CLOCK") (class "Default")
      (node (ref "IC1") (pin "11") (pinfunction "SCK_11") (pintype "input"))
      (node (ref "JP8") (pin "5") (pinfunction "5_5") (pintype "passive"))
      (node (ref "JP9") (pin "5") (pinfunction "5_5") (pintype "passive"))
      (node (ref "SV6") (pin "D10~") (pinfunction "D10~{}_D10~") (pintype "passive"))
    )
    (net (code "78") (name "/MX_DATA") (class "Default")
      (node (ref "IC1") (pin "14") (pinfunction "SER_14") (pintype "input"))
      (node (ref "JP9") (pin "9") (pinfunction "9_9") (pintype "passive"))
      (node (ref "SV6") (pin "D9~") (pinfunction "D9~{}_D9~") (pintype "passive"))
    )
    (net (code "79") (name "/MX_DATAOUT") (class "Default")
      (node (ref "IC1") (pin "9") (pinfunction "QH*_9") (pintype "tri_state"))
      (node (ref "JP8") (pin "9") (pinfunction "9_9") (pintype "passive"))
    )
    (net (code "80") (name "/MX_GND") (class "Default")
      (node (ref "IC1") (pin "13") (pinfunction "G_13") (pintype "input"))
      (node (ref "IC1") (pin "8") (pinfunction "GND_8") (pintype "power_in"))
      (node (ref "JP8") (pin "3") (pinfunction "3_3") (pintype "passive"))
      (node (ref "JP9") (pin "3") (pinfunction "3_3") (pintype "passive"))
      (node (ref "SV6") (pin "GND") (pinfunction "GND_GND") (pintype "passive"))
    )
    (net (code "81") (name "/MX_LATCH") (class "Default")
      (node (ref "IC1") (pin "12") (pinfunction "RCK_12") (pintype "input"))
      (node (ref "JP8") (pin "7") (pinfunction "7_7") (pintype "passive"))
      (node (ref "JP9") (pin "7") (pinfunction "7_7") (pintype "passive"))
      (node (ref "SV6") (pin "A3") (pinfunction "A3_A3") (pintype "passive"))
    )
    (net (code "82") (name "/MX_VCC") (class "Default")
      (node (ref "IC1") (pin "10") (pinfunction "SCL_10") (pintype "input"))
      (node (ref "IC1") (pin "16") (pinfunction "VCC_16") (pintype "power_in"))
      (node (ref "JP8") (pin "1") (pinfunction "1_1") (pintype "passive"))
      (node (ref "JP9") (pin "1") (pinfunction "1_1") (pintype "passive"))
      (node (ref "SV6") (pin "VCC") (pinfunction "VCC_VCC") (pintype "passive"))
    )
    (net (code "83") (name "/N$47") (class "Default")
      (node (ref "SV6") (pin "VSS") (pinfunction "VSS_VSS") (pintype "passive"))
    )
    (net (code "84") (name "/N$49") (class "Default")
      (node (ref "SV6") (pin "A4_SDA") (pinfunction "A4_SDA_A4_SDA") (pintype "passive"))
    )
    (net (code "85") (name "/N$52") (class "Default")
      (node (ref "SV6") (pin "A5_SCL") (pinfunction "A5_SCL_A5_SCL") (pintype "passive"))
    )
    (net (code "86") (name "/N$96") (class "Default")
      (node (ref "JP9") (pin "11") (pinfunction "11_11") (pintype "passive"))
    )
    (net (code "87") (name "/N$97") (class "Default")
      (node (ref "JP9") (pin "13") (pinfunction "13_13") (pintype "passive"))
    )
    (net (code "88") (name "/N$98") (class "Default")
      (node (ref "JP9") (pin "15") (pinfunction "15_15") (pintype "passive"))
    )
    (net (code "89") (name "/N$104") (class "Default")
      (node (ref "JP8") (pin "11") (pinfunction "11_11") (pintype "passive"))
    )
    (net (code "90") (name "/N$105") (class "Default")
      (node (ref "JP8") (pin "13") (pinfunction "13_13") (pintype "passive"))
    )
    (net (code "91") (name "/N$106") (class "Default")
      (node (ref "JP8") (pin "15") (pinfunction "15_15") (pintype "passive"))
    )
    (net (code "92") (name "/PIN3") (class "Default")
      (node (ref "J1") (pin "8") (pinfunction "D3~{}_8") (pintype "passive"))
      (node (ref "U2") (pin "1") (pinfunction "PD3(INT1)_1") (pintype "bidirectional"))
    )
    (net (code "93") (name "/PIN4") (class "Default")
      (node (ref "J1") (pin "10") (pinfunction "D4_10") (pintype "passive"))
      (node (ref "U2") (pin "2") (pinfunction "PD4(XCK/T0)_2") (pintype "bidirectional"))
    )
    (net (code "94") (name "/PIN5") (class "Default")
      (node (ref "J1") (pin "15") (pinfunction "D5~{}_15") (pintype "passive"))
      (node (ref "U2") (pin "9") (pinfunction "PD5(T1)_9") (pintype "bidirectional"))
    )
    (net (code "95") (name "/PIN6") (class "Default")
      (node (ref "J1") (pin "13") (pinfunction "D6~{}_13") (pintype "passive"))
      (node (ref "U2") (pin "10") (pinfunction "PD6(AIN0)_10") (pintype "bidirectional"))
    )
    (net (code "96") (name "/PIN7") (class "Default")
      (node (ref "J1") (pin "11") (pinfunction "D7_11") (pintype "passive"))
      (node (ref "U2") (pin "11") (pinfunction "PD7(AIN1)_11") (pintype "bidirectional"))
    )
    (net (code "97") (name "/PIN8") (class "Default")
      (node (ref "J1") (pin "9") (pinfunction "D8_9") (pintype "passive"))
      (node (ref "U2") (pin "12") (pinfunction "PB0(ICP)_12") (pintype "bidirectional"))
    )
    (net (code "98") (name "/PIN9") (class "Default")
      (node (ref "J1") (pin "7") (pinfunction "D9~{}_7") (pintype "passive"))
      (node (ref "U2") (pin "13") (pinfunction "PB1(OC1A)_13") (pintype "bidirectional"))
    )
    (net (code "99") (name "/PIN10") (class "Default")
      (node (ref "J1") (pin "5") (pinfunction "D10~{}_5") (pintype "passive"))
      (node (ref "U2") (pin "14") (pinfunction "PB2(SS/OC1B)_14") (pintype "bidirectional"))
    )
    (net (code "100") (name "/PWM1") (class "Default")
      (node (ref "SERVOS") (pin "5") (pinfunction "5_5") (pintype "passive"))
      (node (ref "SV1") (pin "D5~") (pinfunction "D5~{}_D5~") (pintype "passive"))
    )
    (net (code "101") (name "/PWM2") (class "Default")
      (node (ref "SERVOS") (pin "6") (pinfunction "6_6") (pintype "passive"))
      (node (ref "SV1") (pin "D6~") (pinfunction "D6~{}_D6~") (pintype "passive"))
    )
    (net (code "102") (name "/RESET") (class "Default")
      (node (ref "R2") (pin "1") (pinfunction "1_1") (pintype "bidirectional"))
      (node (ref "RST") (pin "1") (pinfunction "1_1") (pintype "passive"))
      (node (ref "U2") (pin "29") (pinfunction "PC6(/RESET)_29") (pintype "bidirectional"))
    )
    (net (code "103") (name "/ROW1") (class "Default")
      (node (ref "JP8") (pin "2") (pinfunction "2_2") (pintype "passive"))
      (node (ref "JP9") (pin "2") (pinfunction "2_2") (pintype "passive"))
      (node (ref "LED8") (pin "9") (pinfunction "K1_9") (pintype "bidirectional"))
      (node (ref "R27") (pin "1") (pinfunction "1_1") (pintype "passive"))
    )
    (net (code "104") (name "/ROW2") (class "Default")
      (node (ref "JP8") (pin "4") (pinfunction "4_4") (pintype "passive"))
      (node (ref "JP9") (pin "4") (pinfunction "4_4") (pintype "passive"))
      (node (ref "LED8") (pin "14") (pinfunction "K2_14") (pintype "bidirectional"))
      (node (ref "R28") (pin "1") (pinfunction "1_1") (pintype "passive"))
    )
    (net (code "105") (name "/ROW3") (class "Default")
      (node (ref "JP8") (pin "6") (pinfunction "6_6") (pintype "passive"))
      (node (ref "JP9") (pin "6") (pinfunction "6_6") (pintype "passive"))
      (node (ref "LED8") (pin "8") (pinfunction "K3_8") (pintype "bidirectional"))
      (node (ref "R29") (pin "1") (pinfunction "1_1") (pintype "passive"))
    )
    (net (code "106") (name "/ROW4") (class "Default")
      (node (ref "JP8") (pin "8") (pinfunction "8_8") (pintype "passive"))
      (node (ref "JP9") (pin "8") (pinfunction "8_8") (pintype "passive"))
      (node (ref "LED8") (pin "12") (pinfunction "K4_12") (pintype "bidirectional"))
      (node (ref "R30") (pin "1") (pinfunction "1_1") (pintype "passive"))
    )
    (net (code "107") (name "/ROW5") (class "Default")
      (node (ref "JP8") (pin "10") (pinfunction "10_10") (pintype "passive"))
      (node (ref "JP9") (pin "10") (pinfunction "10_10") (pintype "passive"))
      (node (ref "LED8") (pin "1") (pinfunction "K5_1") (pintype "bidirectional"))
      (node (ref "R26") (pin "2") (pinfunction "2_2") (pintype "passive"))
    )
    (net (code "108") (name "/ROW6") (class "Default")
      (node (ref "JP8") (pin "12") (pinfunction "12_12") (pintype "passive"))
      (node (ref "JP9") (pin "12") (pinfunction "12_12") (pintype "passive"))
      (node (ref "LED8") (pin "7") (pinfunction "K6_7") (pintype "bidirectional"))
      (node (ref "R25") (pin "2") (pinfunction "2_2") (pintype "passive"))
    )
    (net (code "109") (name "/ROW7") (class "Default")
      (node (ref "JP8") (pin "14") (pinfunction "14_14") (pintype "passive"))
      (node (ref "JP9") (pin "14") (pinfunction "14_14") (pintype "passive"))
      (node (ref "LED8") (pin "2") (pinfunction "K7_2") (pintype "bidirectional"))
      (node (ref "R24") (pin "2") (pinfunction "2_2") (pintype "passive"))
    )
    (net (code "110") (name "/ROW8") (class "Default")
      (node (ref "JP8") (pin "16") (pinfunction "16_16") (pintype "passive"))
      (node (ref "JP9") (pin "16") (pinfunction "16_16") (pintype "passive"))
      (node (ref "LED8") (pin "5") (pinfunction "K8_5") (pintype "bidirectional"))
      (node (ref "R23") (pin "2") (pinfunction "2_2") (pintype "passive"))
    )
    (net (code "111") (name "/RXI") (class "Default")
      (node (ref "J1") (pin "4") (pinfunction "D0_RX_4") (pintype "passive"))
      (node (ref "U2") (pin "30") (pinfunction "PD0(RXD)_30") (pintype "bidirectional"))
    )
    (net (code "112") (name "/SCK") (class "Default")
      (node (ref "ANNAREF") (pin "5") (pinfunction "5_5") (pintype "passive"))
      (node (ref "U2") (pin "17") (pinfunction "PB5(SCK)_17") (pintype "bidirectional"))
    )
    (net (code "113") (name "/SCL") (class "Default")
      (node (ref "J1") (pin "3") (pinfunction "A5_SCL_3") (pintype "passive"))
      (node (ref "U2") (pin "28") (pinfunction "PC5(ADC5/SCL)_28") (pintype "bidirectional"))
    )
    (net (code "114") (name "/SDA") (class "Default")
      (node (ref "J1") (pin "1") (pinfunction "A4_SDA_1") (pintype "passive"))
      (node (ref "U2") (pin "27") (pinfunction "PC4(ADC4/SDA)_27") (pintype "bidirectional"))
    )
    (net (code "115") (name "/SM_5V") (class "Default")
      (node (ref "C10") (pin "1") (pinfunction "1_1") (pintype "bidirectional"))
      (node (ref "SERVOS") (pin "3") (pinfunction "3_3") (pintype "passive"))
      (node (ref "SERVOS") (pin "4") (pinfunction "4_4") (pintype "passive"))
      (node (ref "U6") (pin "3") (pinfunction "VOUT_3") (pintype "power_in"))
    )
    (net (code "116") (name "/SM_GND") (class "Default")
      (node (ref "C10") (pin "2") (pinfunction "2_2") (pintype "bidirectional"))
      (node (ref "C9") (pin "2") (pinfunction "2_2") (pintype "bidirectional"))
      (node (ref "SERVOS") (pin "1") (pinfunction "1_1") (pintype "passive"))
      (node (ref "SERVOS") (pin "2") (pinfunction "2_2") (pintype "passive"))
      (node (ref "SV1") (pin "GND") (pinfunction "GND_GND") (pintype "passive"))
      (node (ref "U6") (pin "4") (pinfunction "GND_4") (pintype "power_in"))
    )
    (net (code "117") (name "/SM_VSS") (class "Default")
      (node (ref "C9") (pin "1") (pinfunction "1_1") (pintype "bidirectional"))
      (node (ref "SV1") (pin "VSS") (pinfunction "VSS_VSS") (pintype "passive"))
      (node (ref "U6") (pin "1") (pinfunction "VIN_1") (pintype "power_in"))
    )
    (net (code "118") (name "/TXO") (class "Default")
      (node (ref "J1") (pin "6") (pinfunction "D1_TX_6") (pintype "passive"))
      (node (ref "U2") (pin "31") (pinfunction "PD1(TXD)_31") (pintype "bidirectional"))
    )
    (net (code "119") (name "/VCC2") (class "Default")
      (node (ref "NRF") (pin "2") (pinfunction "2_2") (pintype "passive"))
    )
    (net (code "120") (name "/VSS") (class "Default")
      (node (ref "C1") (pin "1") (pinfunction "1_1") (pintype "bidirectional"))
      (node (ref "C2") (pin "1") (pinfunction "1_1") (pintype "bidirectional"))
      (node (ref "J1") (pin "14") (pinfunction "VSS_14") (pintype "passive"))
      (node (ref "POWER") (pin "1") (pinfunction "1_1") (pintype "passive"))
      (node (ref "U1") (pin "3") (pinfunction "IN_3") (pintype "bidirectional"))
      (node (ref "V") (pin "1") (pinfunction "1_1") (pintype "passive"))
    )
    (net (code "121") (name "3.3V") (class "Default")
      (node (ref "ANNAREF") (pin "2") (pinfunction "2_2") (pintype "passive"))
      (node (ref "C3") (pin "1") (pinfunction "1_1") (pintype "bidirectional"))
      (node (ref "C4") (pin "1") (pinfunction "1_1") (pintype "bidirectional"))
      (node (ref "C8") (pin "1") (pinfunction "1_1") (pintype "bidirectional"))
      (node (ref "J1") (pin "12") (pinfunction "VCC_12") (pintype "passive"))
      (node (ref "R2") (pin "2") (pinfunction "2_2") (pintype "bidirectional"))
      (node (ref "U1") (pin "2") (pinfunction "OUT_2") (pintype "bidirectional"))
      (node (ref "U1") (pin "4") (pinfunction "OUT_4") (pintype "bidirectional"))
      (node (ref "U2") (pin "18") (pinfunction "AVCC_18") (pintype "bidirectional"))
      (node (ref "U2") (pin "4") (pinfunction "VCC_4") (pintype "bidirectional"))
      (node (ref "U2") (pin "6") (pinfunction "VCC_6") (pintype "bidirectional"))
    )
    (net (code "122") (name "DGND") (class "Default")
      (node (ref "-") (pin "1") (pinfunction "P_1") (pintype "passive"))
      (node (ref "3.3VREG") (pin "GND") (pinfunction "GND_GND") (pintype "input"))
      (node (ref "ANNAREF3") (pin "1") (pinfunction "1_1") (pintype "passive"))
      (node (ref "C11") (pin "2") (pinfunction "2_2") (pintype "passive"))
      (node (ref "C12") (pin "2") (pinfunction "2_2") (pintype "passive"))
      (node (ref "C13") (pin "1") (pinfunction "1_1") (pintype "passive"))
      (node (ref "JP4") (pin "4") (pinfunction "4_4") (pintype "passive"))
      (node (ref "R-LED1") (pin "1") (pinfunction "1_1") (pintype "passive"))
      (node (ref "U3") (pin "14") (pinfunction "GND_14") (pintype "passive"))
    )
    (net (code "123") (name "GND") (class "Default")
      (node (ref "ANNAREF") (pin "1") (pinfunction "1_1") (pintype "passive"))
      (node (ref "C1") (pin "2") (pinfunction "2_2") (pintype "bidirectional"))
      (node (ref "C2") (pin "2") (pinfunction "2_2") (pintype "bidirectional"))
      (node (ref "C3") (pin "2") (pinfunction "2_2") (pintype "bidirectional"))
      (node (ref "C4") (pin "2") (pinfunction "2_2") (pintype "bidirectional"))
      (node (ref "C5") (pin "1") (pinfunction "1_1") (pintype "bidirectional"))
      (node (ref "C6") (pin "1") (pinfunction "1_1") (pintype "bidirectional"))
      (node (ref "C7") (pin "2") (pinfunction "2_2") (pintype "bidirectional"))
      (node (ref "C8") (pin "2") (pinfunction "2_2") (pintype "bidirectional"))
      (node (ref "D3") (pin "2") (pinfunction "CATHODE_2") (pintype "bidirectional"))
      (node (ref "J1") (pin "16") (pinfunction "GND_16") (pintype "passive"))
      (node (ref "POWER") (pin "2") (pinfunction "2_2") (pintype "passive"))
      (node (ref "U1") (pin "1") (pinfunction "GND_1") (pintype "bidirectional"))
      (node (ref "U2") (pin "21") (pinfunction "GND_21") (pintype "bidirectional"))
      (node (ref "U2") (pin "3") (pinfunction "GND_3") (pintype "bidirectional"))
      (node (ref "U2") (pin "5") (pinfunction "GND_5") (pintype "bidirectional"))
    )
    (net (code "124") (name "Net-(D1-BLUE_CATHODE)") (class "Default")
      (node (ref "D1") (pin "4") (pinfunction "BLUE_CATHODE_4") (pintype "bidirectional"))
      (node (ref "R1") (pin "1") (pinfunction "1_1") (pintype "passive"))
    )
    (net (code "125") (name "Net-(D1-GREEN_CATHODE)") (class "Default")
      (node (ref "D1") (pin "3") (pinfunction "GREEN_CATHODE_3") (pintype "bidirectional"))
      (node (ref "R3") (pin "1") (pinfunction "1_1") (pintype "passive"))
    )
    (net (code "126") (name "Net-(D1-RED_CATHODE)") (class "Default")
      (node (ref "D1") (pin "1") (pinfunction "RED_CATHODE_1") (pintype "bidirectional"))
      (node (ref "R14") (pin "1") (pinfunction "1_1") (pintype "passive"))
    )
    (net (code "127") (name "Net-(D2-BLUE_CATHODE)") (class "Default")
      (node (ref "D2") (pin "4") (pinfunction "BLUE_CATHODE_4") (pintype "bidirectional"))
      (node (ref "R4") (pin "2") (pinfunction "2_2") (pintype "passive"))
    )
    (net (code "128") (name "Net-(D2-GREEN_CATHODE)") (class "Default")
      (node (ref "D2") (pin "3") (pinfunction "GREEN_CATHODE_3") (pintype "bidirectional"))
      (node (ref "R5") (pin "2") (pinfunction "2_2") (pintype "passive"))
    )
    (net (code "129") (name "Net-(D2-RED_CATHODE)") (class "Default")
      (node (ref "D2") (pin "1") (pinfunction "RED_CATHODE_1") (pintype "bidirectional"))
      (node (ref "R15") (pin "2") (pinfunction "2_2") (pintype "passive"))
    )
    (net (code "130") (name "Net-(D3-BLUE_CATHODE)") (class "Default")
      (node (ref "D3") (pin "4") (pinfunction "BLUE_CATHODE_4") (pintype "bidirectional"))
      (node (ref "R22") (pin "1") (pinfunction "1_1") (pintype "bidirectional"))
    )
    (net (code "131") (name "Net-(D3-GREEN_CATHODE)") (class "Default")
      (node (ref "D3") (pin "3") (pinfunction "GREEN_CATHODE_3") (pintype "bidirectional"))
      (node (ref "R21") (pin "1") (pinfunction "1_1") (pintype "bidirectional"))
    )
    (net (code "132") (name "Net-(D3-RED_CATHODE)") (class "Default")
      (node (ref "D3") (pin "1") (pinfunction "RED_CATHODE_1") (pintype "bidirectional"))
      (node (ref "R20") (pin "1") (pinfunction "1_1") (pintype "bidirectional"))
    )
    (net (code "133") (name "Net-(JP1-Pad1)") (class "Default")
      (node (ref "JP1") (pin "1") (pinfunction "1_1") (pintype "passive"))
      (node (ref "R12") (pin "2") (pinfunction "2_2") (pintype "passive"))
      (node (ref "R13") (pin "2") (pinfunction "2_2") (pintype "passive"))
      (node (ref "SV4") (pin "VCC") (pinfunction "VCC_VCC") (pintype "passive"))
    )
    (net (code "134") (name "Net-(JP1-Pad3)") (class "Default")
      (node (ref "JP1") (pin "3") (pinfunction "3_3") (pintype "passive"))
      (node (ref "SV4") (pin "GND") (pinfunction "GND_GND") (pintype "passive"))
    )
    (net (code "135") (name "Net-(JP1-Pad4)") (class "Default")
      (node (ref "JP1") (pin "4") (pinfunction "4_4") (pintype "passive"))
      (node (ref "R12") (pin "1") (pinfunction "1_1") (pintype "passive"))
      (node (ref "SV4") (pin "A5_SCL") (pinfunction "A5_SCL_A5_SCL") (pintype "passive"))
    )
    (net (code "136") (name "Net-(JP1-Pad5)") (class "Default")
      (node (ref "JP1") (pin "5") (pinfunction "5_5") (pintype "passive"))
      (node (ref "R13") (pin "1") (pinfunction "1_1") (pintype "passive"))
      (node (ref "SV4") (pin "A4_SDA") (pinfunction "A4_SDA_A4_SDA") (pintype "passive"))
    )
    (net (code "137") (name "Net-(JP2-Pad1)") (class "Default")
      (node (ref "JP2") (pin "1") (pinfunction "1_1") (pintype "passive"))
      (node (ref "R1") (pin "2") (pinfunction "2_2") (pintype "passive"))
    )
    (net (code "138") (name "Net-(JP2-Pad3)") (class "Default")
      (node (ref "JP2") (pin "3") (pinfunction "3_3") (pintype "passive"))
      (node (ref "R3") (pin "2") (pinfunction "2_2") (pintype "passive"))
    )
    (net (code "139") (name "Net-(JP2-Pad17)") (class "Default")
      (node (ref "JP2") (pin "17") (pinfunction "17_17") (pintype "passive"))
      (node (ref "R14") (pin "2") (pinfunction "2_2") (pintype "passive"))
    )
    (net (code "140") (name "Net-(JP10-Pad1)") (class "Default")
      (node (ref "JP10") (pin "1") (pinfunction "1_1") (pintype "passive"))
      (node (ref "SV7") (pin "A4_SDA") (pinfunction "A4_SDA_A4_SDA") (pintype "passive"))
    )
    (net (code "141") (name "Net-(JP10-Pad2)") (class "Default")
      (node (ref "JP10") (pin "2") (pinfunction "2_2") (pintype "passive"))
      (node (ref "SV7") (pin "A5_SCL") (pinfunction "A5_SCL_A5_SCL") (pintype "passive"))
    )
    (net (code "142") (name "Net-(JP10-Pad5)") (class "Default")
      (node (ref "JP10") (pin "5") (pinfunction "5_5") (pintype "passive"))
      (node (ref "SV7") (pin "D8") (pinfunction "D8_D8") (pintype "passive"))
    )
    (net (code "143") (name "Net-(JP10-Pad6)") (class "Default")
      (node (ref "JP10") (pin "6") (pinfunction "6_6") (pintype "passive"))
      (node (ref "SV7") (pin "D7") (pinfunction "D7_D7") (pintype "passive"))
    )
    (net (code "144") (name "Net-(JP11-Pad1)") (class "Default")
      (node (ref "JP11") (pin "1") (pinfunction "1_1") (pintype "passive"))
      (node (ref "SV7") (pin "A3") (pinfunction "A3_A3") (pintype "passive"))
    )
    (net (code "145") (name "Net-(JP11-Pad2)") (class "Default")
      (node (ref "JP11") (pin "2") (pinfunction "2_2") (pintype "passive"))
      (node (ref "SV7") (pin "D0_RX") (pinfunction "D0_RX_D0_RX") (pintype "passive"))
    )
    (net (code "146") (name "Net-(JP11-Pad3)") (class "Default")
      (node (ref "JP11") (pin "3") (pinfunction "3_3") (pintype "passive"))
      (node (ref "SV7") (pin "D1_TX") (pinfunction "D1_TX_D1_TX") (pintype "passive"))
    )
    (net (code "147") (name "Net-(JP11-Pad5)") (class "Default")
      (node (ref "JP11") (pin "5") (pinfunction "5_5") (pintype "passive"))
      (node (ref "SV7") (pin "D4") (pinfunction "D4_D4") (pintype "passive"))
    )
    (net (code "148") (name "Net-(JP11-Pad6)") (class "Default")
      (node (ref "JP11") (pin "6") (pinfunction "6_6") (pintype "passive"))
      (node (ref "SV7") (pin "VCC") (pinfunction "VCC_VCC") (pintype "passive"))
    )
    (net (code "149") (name "Net-(JP11-Pad7)") (class "Default")
      (node (ref "JP11") (pin "7") (pinfunction "7_7") (pintype "passive"))
      (node (ref "SV7") (pin "VSS") (pinfunction "VSS_VSS") (pintype "passive"))
    )
    (net (code "150") (name "Net-(JP11-Pad8)") (class "Default")
      (node (ref "JP11") (pin "8") (pinfunction "8_8") (pintype "passive"))
      (node (ref "SV7") (pin "GND") (pinfunction "GND_GND") (pintype "passive"))
    )
    (net (code "151") (name "Net-(K2-B0)") (class "Default")
      (node (ref "K2") (pin "4") (pinfunction "B0_4") (pintype "bidirectional"))
      (node (ref "R8") (pin "2") (pinfunction "2_2") (pintype "passive"))
    )
    (net (code "152") (name "Net-(K3-B0)") (class "Default")
      (node (ref "K3") (pin "4") (pinfunction "B0_4") (pintype "bidirectional"))
      (node (ref "R9") (pin "2") (pinfunction "2_2") (pintype "passive"))
    )
    (net (code "153") (name "Net-(LED1-C)") (class "Default")
      (node (ref "LED1") (pin "K") (pinfunction "C_K") (pintype "passive"))
      (node (ref "R-LED1") (pin "2") (pinfunction "2_2") (pintype "passive"))
    )
    (net (code "154") (name "Net-(LED3-PadA)") (class "Default")
      (node (ref "LED3") (pin "A") (pinfunction "A_A") (pintype "passive"))
      (node (ref "R6") (pin "1") (pinfunction "1_1") (pintype "passive"))
    )
    (net (code "155") (name "Net-(LED4-PadA)") (class "Default")
      (node (ref "LED4") (pin "A") (pinfunction "A_A") (pintype "passive"))
      (node (ref "R7") (pin "1") (pinfunction "1_1") (pintype "passive"))
    )
    (net (code "156") (name "Net-(LED9-PadA)") (class "Default")
      (node (ref "LED9") (pin "A") (pinfunction "A_A") (pintype "passive"))
      (node (ref "R16") (pin "1") (pinfunction "1_1") (pintype "passive"))
    )
    (net (code "157") (name "Net-(LED10-PadA)") (class "Default")
      (node (ref "LED10") (pin "A") (pinfunction "A_A") (pintype "passive"))
      (node (ref "R17") (pin "1") (pinfunction "1_1") (pintype "passive"))
    )
    (net (code "158") (name "Net-(LED10-PadC)") (class "Default")
      (node (ref "LED10") (pin "C") (pinfunction "C_C") (pintype "passive"))
      (node (ref "LED11") (pin "C") (pinfunction "C_C") (pintype "passive"))
      (node (ref "LED12") (pin "C") (pinfunction "C_C") (pintype "passive"))
      (node (ref "LED9") (pin "C") (pinfunction "C_C") (pintype "passive"))
      (node (ref "SV8") (pin "GND") (pinfunction "GND_GND") (pintype "passive"))
    )
    (net (code "159") (name "Net-(LED11-PadA)") (class "Default")
      (node (ref "LED11") (pin "A") (pinfunction "A_A") (pintype "passive"))
      (node (ref "R18") (pin "1") (pinfunction "1_1") (pintype "passive"))
    )
    (net (code "160") (name "Net-(LED12-PadA)") (class "Default")
      (node (ref "LED12") (pin "A") (pinfunction "A_A") (pintype "passive"))
      (node (ref "R19") (pin "1") (pinfunction "1_1") (pintype "passive"))
    )
    (net (code "161") (name "Net-(R23-Pad1)") (class "Default")
      (node (ref "R23") (pin "1") (pinfunction "1_1") (pintype "passive"))
      (node (ref "SV6") (pin "D8") (pinfunction "D8_D8") (pintype "passive"))
    )
    (net (code "162") (name "Net-(R24-Pad1)") (class "Default")
      (node (ref "R24") (pin "1") (pinfunction "1_1") (pintype "passive"))
      (node (ref "SV6") (pin "D7") (pinfunction "D7_D7") (pintype "passive"))
    )
    (net (code "163") (name "Net-(R27-Pad2)") (class "Default")
      (node (ref "R27") (pin "2") (pinfunction "2_2") (pintype "passive"))
      (node (ref "SV6") (pin "D0_RX") (pinfunction "D0_RX_D0_RX") (pintype "passive"))
    )
    (net (code "164") (name "Net-(R28-Pad2)") (class "Default")
      (node (ref "R28") (pin "2") (pinfunction "2_2") (pintype "passive"))
      (node (ref "SV6") (pin "D1_TX") (pinfunction "D1_TX_D1_TX") (pintype "passive"))
    )
    (net (code "165") (name "Net-(R30-Pad2)") (class "Default")
      (node (ref "R30") (pin "2") (pinfunction "2_2") (pintype "passive"))
      (node (ref "SV6") (pin "D4") (pinfunction "D4_D4") (pintype "passive"))
    )
    (net (code "166") (name "Net-(SV2-D5~{})") (class "Default")
      (node (ref "SV2") (pin "D5~") (pinfunction "D5~{}_D5~") (pintype "passive"))
      (node (ref "U5") (pin "6") (pinfunction "IA_6") (pintype "power_in"))
    )
    (net (code "167") (name "Net-(SV2-D6~{})") (class "Default")
      (node (ref "SV2") (pin "D6~") (pinfunction "D6~{}_D6~") (pintype "passive"))
      (node (ref "U5") (pin "7") (pinfunction "IB_7") (pintype "power_in"))
    )
    (net (code "168") (name "Net-(SV5-A4_SDA)") (class "Default")
      (node (ref "SV5") (pin "1") (pinfunction "A4_SDA_1") (pintype "passive"))
      (node (ref "U$1") (pin "A4") (pinfunction "A4_A4") (pintype "bidirectional"))
    )
    (net (code "169") (name "Net-(SV5-A5_SCL)") (class "Default")
      (node (ref "SV5") (pin "3") (pinfunction "A5_SCL_3") (pintype "passive"))
      (node (ref "U$1") (pin "A5") (pinfunction "A5_A5") (pintype "bidirectional"))
    )
    (net (code "170") (name "Net-(SV5-D0_RX)") (class "Default")
      (node (ref "SV5") (pin "4") (pinfunction "D0_RX_4") (pintype "passive"))
      (node (ref "U$1") (pin "2") (pinfunction "RXI_2") (pintype "bidirectional"))
    )
    (net (code "171") (name "Net-(SV5-D1_TX)") (class "Default")
      (node (ref "SV5") (pin "6") (pinfunction "D1_TX_6") (pintype "passive"))
      (node (ref "U$1") (pin "1") (pinfunction "TXO_1") (pintype "bidirectional"))
    )
    (net (code "172") (name "Net-(SV5-D3~{})") (class "Default")
      (node (ref "SV5") (pin "8") (pinfunction "D3~{}_8") (pintype "passive"))
      (node (ref "U$1") (pin "6") (pinfunction "*3_6") (pintype "bidirectional"))
    )
    (net (code "173") (name "Net-(SV5-D4)") (class "Default")
      (node (ref "SV5") (pin "10") (pinfunction "D4_10") (pintype "passive"))
      (node (ref "U$1") (pin "7") (pinfunction "4_7") (pintype "bidirectional"))
    )
    (net (code "174") (name "Net-(SV5-D5~{})") (class "Default")
      (node (ref "SV5") (pin "15") (pinfunction "D5~{}_15") (pintype "passive"))
      (node (ref "U$1") (pin "8") (pinfunction "*5_8") (pintype "bidirectional"))
    )
    (net (code "175") (name "Net-(SV5-D6~{})") (class "Default")
      (node (ref "SV5") (pin "13") (pinfunction "D6~{}_13") (pintype "passive"))
      (node (ref "U$1") (pin "9") (pinfunction "*6_9") (pintype "bidirectional"))
    )
    (net (code "176") (name "Net-(SV5-D7)") (class "Default")
      (node (ref "SV5") (pin "11") (pinfunction "D7_11") (pintype "passive"))
      (node (ref "U$1") (pin "10") (pinfunction "7_10") (pintype "bidirectional"))
    )
    (net (code "177") (name "Net-(SV5-D8)") (class "Default")
      (node (ref "SV5") (pin "9") (pinfunction "D8_9") (pintype "passive"))
      (node (ref "U$1") (pin "11") (pinfunction "8_11") (pintype "bidirectional"))
    )
    (net (code "178") (name "Net-(SV5-D9~{})") (class "Default")
      (node (ref "SV5") (pin "7") (pinfunction "D9~{}_7") (pintype "passive"))
      (node (ref "U$1") (pin "12") (pinfunction "*9_12") (pintype "bidirectional"))
    )
    (net (code "179") (name "Net-(SV5-D10~{})") (class "Default")
      (node (ref "SV5") (pin "5") (pinfunction "D10~{}_5") (pintype "passive"))
      (node (ref "U$1") (pin "13") (pinfunction "*10_13") (pintype "bidirectional"))
    )
    (net (code "180") (name "Net-(SV6-D3~{})") (class "Default")
      (node (ref "R29") (pin "2") (pinfunction "2_2") (pintype "passive"))
      (node (ref "SV6") (pin "D3~") (pinfunction "D3~{}_D3~") (pintype "passive"))
    )
    (net (code "181") (name "Net-(SV6-D5~{})") (class "Default")
      (node (ref "R26") (pin "1") (pinfunction "1_1") (pintype "passive"))
      (node (ref "SV6") (pin "D5~") (pinfunction "D5~{}_D5~") (pintype "passive"))
    )
    (net (code "182") (name "Net-(SV6-D6~{})") (class "Default")
      (node (ref "R25") (pin "1") (pinfunction "1_1") (pintype "passive"))
      (node (ref "SV6") (pin "D6~") (pinfunction "D6~{}_D6~") (pintype "passive"))
    )
    (net (code "183") (name "Net-(SV7-D3~{})") (class "Default")
      (node (ref "JP11") (pin "4") (pinfunction "4_4") (pintype "passive"))
      (node (ref "SV7") (pin "D3~") (pinfunction "D3~{}_D3~") (pintype "passive"))
    )
    (net (code "184") (name "Net-(SV7-D5~{})") (class "Default")
      (node (ref "JP10") (pin "8") (pinfunction "8_8") (pintype "passive"))
      (node (ref "SV7") (pin "D5~") (pinfunction "D5~{}_D5~") (pintype "passive"))
    )
    (net (code "185") (name "Net-(SV7-D6~{})") (class "Default")
      (node (ref "JP10") (pin "7") (pinfunction "7_7") (pintype "passive"))
      (node (ref "SV7") (pin "D6~") (pinfunction "D6~{}_D6~") (pintype "passive"))
    )
    (net (code "186") (name "Net-(SV7-D9~{})") (class "Default")
      (node (ref "JP10") (pin "4") (pinfunction "4_4") (pintype "passive"))
      (node (ref "SV7") (pin "D9~") (pinfunction "D9~{}_D9~") (pintype "passive"))
    )
    (net (code "187") (name "Net-(SV7-D10~{})") (class "Default")
      (node (ref "JP10") (pin "3") (pinfunction "3_3") (pintype "passive"))
      (node (ref "SV7") (pin "D10~") (pinfunction "D10~{}_D10~") (pintype "passive"))
    )
    (net (code "188") (name "Net-(SW1-P)") (class "Default")
      (node (ref "R10") (pin "1") (pinfunction "1_1") (pintype "passive"))
      (node (ref "SV3") (pin "D0_RX") (pinfunction "D0_RX_D0_RX") (pintype "passive"))
      (node (ref "SW1") (pin "A") (pinfunction "P_A") (pintype "passive"))
    )
    (net (code "189") (name "Net-(SW1-S)") (class "Default")
      (node (ref "SV3") (pin "GND") (pinfunction "GND_GND") (pintype "passive"))
      (node (ref "SW1") (pin "B") (pinfunction "S_B") (pintype "passive"))
      (node (ref "SW1") (pin "B'") (pinfunction "S1_B'") (pintype "passive"))
      (node (ref "SW2") (pin "B") (pinfunction "S_B") (pintype "passive"))
      (node (ref "SW2") (pin "B'") (pinfunction "S1_B'") (pintype "passive"))
    )
    (net (code "190") (name "Net-(SW2-P)") (class "Default")
      (node (ref "R11") (pin "1") (pinfunction "1_1") (pintype "passive"))
      (node (ref "SV3") (pin "D1_TX") (pinfunction "D1_TX_D1_TX") (pintype "passive"))
      (node (ref "SW2") (pin "A") (pinfunction "P_A") (pintype "passive"))
    )
    (net (code "191") (name "Net-(U$1-A0)") (class "Default")
      (node (ref "R4") (pin "1") (pinfunction "1_1") (pintype "passive"))
      (node (ref "U$1") (pin "17") (pinfunction "A0_17") (pintype "bidirectional"))
    )
    (net (code "192") (name "Net-(U$1-A1)") (class "Default")
      (node (ref "R5") (pin "1") (pinfunction "1_1") (pintype "passive"))
      (node (ref "U$1") (pin "18") (pinfunction "A1_18") (pintype "bidirectional"))
    )
    (net (code "193") (name "Net-(U$1-A2)") (class "Default")
      (node (ref "R15") (pin "1") (pinfunction "1_1") (pintype "passive"))
      (node (ref "U$1") (pin "19") (pinfunction "A2_19") (pintype "bidirectional"))
    )
    (net (code "194") (name "Net-(U2-AREF)") (class "Default")
      (node (ref "C7") (pin "1") (pinfunction "1_1") (pintype "bidirectional"))
      (node (ref "U2") (pin "20") (pinfunction "AREF_20") (pintype "bidirectional"))
    )
    (net (code "195") (name "Net-(U2-PB6(XTAL1{slash}TOSC1))") (class "Default")
      (node (ref "C6") (pin "2") (pinfunction "2_2") (pintype "bidirectional"))
      (node (ref "Q1") (pin "2") (pinfunction "2_2") (pintype "passive"))
      (node (ref "U2") (pin "7") (pinfunction "PB6(XTAL1/TOSC1)_7") (pintype "bidirectional"))
    )
    (net (code "196") (name "Net-(U2-PB7(XTAL2{slash}TOSC2))") (class "Default")
      (node (ref "C5") (pin "2") (pinfunction "2_2") (pintype "bidirectional"))
      (node (ref "Q1") (pin "1") (pinfunction "1_1") (pintype "passive"))
      (node (ref "U2") (pin "8") (pinfunction "PB7(XTAL2/TOSC2)_8") (pintype "bidirectional"))
    )
    (net (code "197") (name "Net-(U5-OA)") (class "Default")
      (node (ref "J3") (pin "1") (pinfunction "1_1") (pintype "bidirectional"))
      (node (ref "U5") (pin "1") (pinfunction "OA_1") (pintype "input"))
    )
    (net (code "198") (name "Net-(U5-OB)") (class "Default")
      (node (ref "J3") (pin "2") (pinfunction "2_2") (pintype "bidirectional"))
      (node (ref "U5") (pin "4") (pinfunction "OB_4") (pintype "input"))
    )
    (net (code "199") (name "unconnected-(JP1-Pad2)") (class "Default")
      (node (ref "JP1") (pin "2") (pinfunction "2_2") (pintype "passive"))
    )
    (net (code "200") (name "unconnected-(JP1-Pad6)") (class "Default")
      (node (ref "JP1") (pin "6") (pinfunction "6_6") (pintype "passive"))
    )
    (net (code "201") (name "unconnected-(JP1-Pad7)") (class "Default")
      (node (ref "JP1") (pin "7") (pinfunction "7_7") (pintype "passive"))
    )
    (net (code "202") (name "unconnected-(JP1-Pad8)") (class "Default")
      (node (ref "JP1") (pin "8") (pinfunction "8_8") (pintype "passive"))
    )
    (net (code "203") (name "unconnected-(JP2-Pad2)") (class "Default")
      (node (ref "JP2") (pin "2") (pinfunction "2_2") (pintype "passive"))
    )
    (net (code "204") (name "unconnected-(JP2-Pad4)") (class "Default")
      (node (ref "JP2") (pin "4") (pinfunction "4_4") (pintype "passive"))
    )
    (net (code "205") (name "unconnected-(JP2-Pad5)") (class "Default")
      (node (ref "JP2") (pin "5") (pinfunction "5_5") (pintype "passive"))
    )
    (net (code "206") (name "unconnected-(JP2-Pad6)") (class "Default")
      (node (ref "JP2") (pin "6") (pinfunction "6_6") (pintype "passive"))
    )
    (net (code "207") (name "unconnected-(JP2-Pad8)") (class "Default")
      (node (ref "JP2") (pin "8") (pinfunction "8_8") (pintype "passive"))
    )
    (net (code "208") (name "unconnected-(JP2-Pad10)") (class "Default")
      (node (ref "JP2") (pin "10") (pinfunction "10_10") (pintype "passive"))
    )
    (net (code "209") (name "unconnected-(JP2-Pad12)") (class "Default")
      (node (ref "JP2") (pin "12") (pinfunction "12_12") (pintype "passive"))
    )
    (net (code "210") (name "unconnected-(JP2-Pad14)") (class "Default")
      (node (ref "JP2") (pin "14") (pinfunction "14_14") (pintype "passive"))
    )
    (net (code "211") (name "unconnected-(JP2-Pad16)") (class "Default")
      (node (ref "JP2") (pin "16") (pinfunction "16_16") (pintype "passive"))
    )
    (net (code "212") (name "unconnected-(JP3-Pad1)") (class "Default")
      (node (ref "JP3") (pin "1") (pinfunction "1_1") (pintype "passive"))
    )
    (net (code "213") (name "unconnected-(JP3-Pad2)") (class "Default")
      (node (ref "JP3") (pin "2") (pinfunction "2_2") (pintype "passive"))
    )
    (net (code "214") (name "unconnected-(JP3-Pad3)") (class "Default")
      (node (ref "JP3") (pin "3") (pinfunction "3_3") (pintype "passive"))
    )
    (net (code "215") (name "unconnected-(JP3-Pad4)") (class "Default")
      (node (ref "JP3") (pin "4") (pinfunction "4_4") (pintype "passive"))
    )
    (net (code "216") (name "unconnected-(JP3-Pad5)") (class "Default")
      (node (ref "JP3") (pin "5") (pinfunction "5_5") (pintype "passive"))
    )
    (net (code "217") (name "unconnected-(JP3-Pad6)") (class "Default")
      (node (ref "JP3") (pin "6") (pinfunction "6_6") (pintype "passive"))
    )
    (net (code "218") (name "unconnected-(JP3-Pad7)") (class "Default")
      (node (ref "JP3") (pin "7") (pinfunction "7_7") (pintype "passive"))
    )
    (net (code "219") (name "unconnected-(JP3-Pad8)") (class "Default")
      (node (ref "JP3") (pin "8") (pinfunction "8_8") (pintype "passive"))
    )
    (net (code "220") (name "unconnected-(K2-A1-Pad2)") (class "Default")
      (node (ref "K2") (pin "2") (pinfunction "A1_2") (pintype "bidirectional"))
    )
    (net (code "221") (name "unconnected-(K2-B1-Pad3)") (class "Default")
      (node (ref "K2") (pin "3") (pinfunction "B1_3") (pintype "bidirectional"))
    )
    (net (code "222") (name "unconnected-(K3-A1-Pad2)") (class "Default")
      (node (ref "K3") (pin "2") (pinfunction "A1_2") (pintype "bidirectional"))
    )
    (net (code "223") (name "unconnected-(K3-B1-Pad3)") (class "Default")
      (node (ref "K3") (pin "3") (pinfunction "B1_3") (pintype "bidirectional"))
    )
    (net (code "224") (name "unconnected-(SV1-D3~{}-PadD3~)") (class "Default")
      (node (ref "SV1") (pin "D3~") (pinfunction "D3~{}_D3~") (pintype "passive"))
    )
    (net (code "225") (name "unconnected-(SV1-D9~{}-PadD9~)") (class "Default")
      (node (ref "SV1") (pin "D9~") (pinfunction "D9~{}_D9~") (pintype "passive"))
    )
    (net (code "226") (name "unconnected-(SV1-D10~{}-PadD10~)") (class "Default")
      (node (ref "SV1") (pin "D10~") (pinfunction "D10~{}_D10~") (pintype "passive"))
    )
    (net (code "227") (name "unconnected-(SV1-PadA3)") (class "Default")
      (node (ref "SV1") (pin "A3") (pinfunction "A3_A3") (pintype "passive"))
    )
    (net (code "228") (name "unconnected-(SV1-PadA4_SDA)") (class "Default")
      (node (ref "SV1") (pin "A4_SDA") (pinfunction "A4_SDA_A4_SDA") (pintype "passive"))
    )
    (net (code "229") (name "unconnected-(SV1-PadA5_SCL)") (class "Default")
      (node (ref "SV1") (pin "A5_SCL") (pinfunction "A5_SCL_A5_SCL") (pintype "passive"))
    )
    (net (code "230") (name "unconnected-(SV1-PadD0_RX)") (class "Default")
      (node (ref "SV1") (pin "D0_RX") (pinfunction "D0_RX_D0_RX") (pintype "passive"))
    )
    (net (code "231") (name "unconnected-(SV1-PadD1_TX)") (class "Default")
      (node (ref "SV1") (pin "D1_TX") (pinfunction "D1_TX_D1_TX") (pintype "passive"))
    )
    (net (code "232") (name "unconnected-(SV1-PadD4)") (class "Default")
      (node (ref "SV1") (pin "D4") (pinfunction "D4_D4") (pintype "passive"))
    )
    (net (code "233") (name "unconnected-(SV1-PadD7)") (class "Default")
      (node (ref "SV1") (pin "D7") (pinfunction "D7_D7") (pintype "passive"))
    )
    (net (code "234") (name "unconnected-(SV1-PadD8)") (class "Default")
      (node (ref "SV1") (pin "D8") (pinfunction "D8_D8") (pintype "passive"))
    )
    (net (code "235") (name "unconnected-(SV1-PadVCC)") (class "Default")
      (node (ref "SV1") (pin "VCC") (pinfunction "VCC_VCC") (pintype "passive"))
    )
    (net (code "236") (name "unconnected-(SV2-D3~{}-PadD3~)") (class "Default")
      (node (ref "SV2") (pin "D3~") (pinfunction "D3~{}_D3~") (pintype "passive"))
    )
    (net (code "237") (name "unconnected-(SV2-D9~{}-PadD9~)") (class "Default")
      (node (ref "SV2") (pin "D9~") (pinfunction "D9~{}_D9~") (pintype "passive"))
    )
    (net (code "238") (name "unconnected-(SV2-D10~{}-PadD10~)") (class "Default")
      (node (ref "SV2") (pin "D10~") (pinfunction "D10~{}_D10~") (pintype "passive"))
    )
    (net (code "239") (name "unconnected-(SV2-PadA3)") (class "Default")
      (node (ref "SV2") (pin "A3") (pinfunction "A3_A3") (pintype "passive"))
    )
    (net (code "240") (name "unconnected-(SV2-PadA4_SDA)") (class "Default")
      (node (ref "SV2") (pin "A4_SDA") (pinfunction "A4_SDA_A4_SDA") (pintype "passive"))
    )
    (net (code "241") (name "unconnected-(SV2-PadD0_RX)") (class "Default")
      (node (ref "SV2") (pin "D0_RX") (pinfunction "D0_RX_D0_RX") (pintype "passive"))
    )
    (net (code "242") (name "unconnected-(SV2-PadD1_TX)") (class "Default")
      (node (ref "SV2") (pin "D1_TX") (pinfunction "D1_TX_D1_TX") (pintype "passive"))
    )
    (net (code "243") (name "unconnected-(SV2-PadD4)") (class "Default")
      (node (ref "SV2") (pin "D4") (pinfunction "D4_D4") (pintype "passive"))
    )
    (net (code "244") (name "unconnected-(SV2-PadD7)") (class "Default")
      (node (ref "SV2") (pin "D7") (pinfunction "D7_D7") (pintype "passive"))
    )
    (net (code "245") (name "unconnected-(SV2-PadD8)") (class "Default")
      (node (ref "SV2") (pin "D8") (pinfunction "D8_D8") (pintype "passive"))
    )
    (net (code "246") (name "unconnected-(SV2-PadVCC)") (class "Default")
      (node (ref "SV2") (pin "VCC") (pinfunction "VCC_VCC") (pintype "passive"))
    )
    (net (code "247") (name "unconnected-(SV2-PadVSS)") (class "Default")
      (node (ref "SV2") (pin "VSS") (pinfunction "VSS_VSS") (pintype "passive"))
    )
    (net (code "248") (name "unconnected-(SV3-D3~{}-PadD3~)") (class "Default")
      (node (ref "SV3") (pin "D3~") (pinfunction "D3~{}_D3~") (pintype "passive"))
    )
    (net (code "249") (name "unconnected-(SV3-D5~{}-PadD5~)") (class "Default")
      (node (ref "SV3") (pin "D5~") (pinfunction "D5~{}_D5~") (pintype "passive"))
    )
    (net (code "250") (name "unconnected-(SV3-D6~{}-PadD6~)") (class "Default")
      (node (ref "SV3") (pin "D6~") (pinfunction "D6~{}_D6~") (pintype "passive"))
    )
    (net (code "251") (name "unconnected-(SV3-D9~{}-PadD9~)") (class "Default")
      (node (ref "SV3") (pin "D9~") (pinfunction "D9~{}_D9~") (pintype "passive"))
    )
    (net (code "252") (name "unconnected-(SV3-D10~{}-PadD10~)") (class "Default")
      (node (ref "SV3") (pin "D10~") (pinfunction "D10~{}_D10~") (pintype "passive"))
    )
    (net (code "253") (name "unconnected-(SV3-PadA3)") (class "Default")
      (node (ref "SV3") (pin "A3") (pinfunction "A3_A3") (pintype "passive"))
    )
    (net (code "254") (name "unconnected-(SV3-PadA4_SDA)") (class "Default")
      (node (ref "SV3") (pin "A4_SDA") (pinfunction "A4_SDA_A4_SDA") (pintype "passive"))
    )
    (net (code "255") (name "unconnected-(SV3-PadA5_SCL)") (class "Default")
      (node (ref "SV3") (pin "A5_SCL") (pinfunction "A5_SCL_A5_SCL") (pintype "passive"))
    )
    (net (code "256") (name "unconnected-(SV3-PadD4)") (class "Default")
      (node (ref "SV3") (pin "D4") (pinfunction "D4_D4") (pintype "passive"))
    )
    (net (code "257") (name "unconnected-(SV3-PadD7)") (class "Default")
      (node (ref "SV3") (pin "D7") (pinfunction "D7_D7") (pintype "passive"))
    )
    (net (code "258") (name "unconnected-(SV3-PadD8)") (class "Default")
      (node (ref "SV3") (pin "D8") (pinfunction "D8_D8") (pintype "passive"))
    )
    (net (code "259") (name "unconnected-(SV3-PadVSS)") (class "Default")
      (node (ref "SV3") (pin "VSS") (pinfunction "VSS_VSS") (pintype "passive"))
    )
    (net (code "260") (name "unconnected-(SV4-D3~{}-PadD3~)") (class "Default")
      (node (ref "SV4") (pin "D3~") (pinfunction "D3~{}_D3~") (pintype "passive"))
    )
    (net (code "261") (name "unconnected-(SV4-D5~{}-PadD5~)") (class "Default")
      (node (ref "SV4") (pin "D5~") (pinfunction "D5~{}_D5~") (pintype "passive"))
    )
    (net (code "262") (name "unconnected-(SV4-D6~{}-PadD6~)") (class "Default")
      (node (ref "SV4") (pin "D6~") (pinfunction "D6~{}_D6~") (pintype "passive"))
    )
    (net (code "263") (name "unconnected-(SV4-D9~{}-PadD9~)") (class "Default")
      (node (ref "SV4") (pin "D9~") (pinfunction "D9~{}_D9~") (pintype "passive"))
    )
    (net (code "264") (name "unconnected-(SV4-D10~{}-PadD10~)") (class "Default")
      (node (ref "SV4") (pin "D10~") (pinfunction "D10~{}_D10~") (pintype "passive"))
    )
    (net (code "265") (name "unconnected-(SV4-PadA3)") (class "Default")
      (node (ref "SV4") (pin "A3") (pinfunction "A3_A3") (pintype "passive"))
    )
    (net (code "266") (name "unconnected-(SV4-PadD0_RX)") (class "Default")
      (node (ref "SV4") (pin "D0_RX") (pinfunction "D0_RX_D0_RX") (pintype "passive"))
    )
    (net (code "267") (name "unconnected-(SV4-PadD1_TX)") (class "Default")
      (node (ref "SV4") (pin "D1_TX") (pinfunction "D1_TX_D1_TX") (pintype "passive"))
    )
    (net (code "268") (name "unconnected-(SV4-PadD4)") (class "Default")
      (node (ref "SV4") (pin "D4") (pinfunction "D4_D4") (pintype "passive"))
    )
    (net (code "269") (name "unconnected-(SV4-PadD7)") (class "Default")
      (node (ref "SV4") (pin "D7") (pinfunction "D7_D7") (pintype "passive"))
    )
    (net (code "270") (name "unconnected-(SV4-PadD8)") (class "Default")
      (node (ref "SV4") (pin "D8") (pinfunction "D8_D8") (pintype "passive"))
    )
    (net (code "271") (name "unconnected-(SV4-PadVSS)") (class "Default")
      (node (ref "SV4") (pin "VSS") (pinfunction "VSS_VSS") (pintype "passive"))
    )
    (net (code "272") (name "unconnected-(SV8-D10~{}-PadD10~)") (class "Default")
      (node (ref "SV8") (pin "D10~") (pinfunction "D10~{}_D10~") (pintype "passive"))
    )
    (net (code "273") (name "unconnected-(SV8-PadA3)") (class "Default")
      (node (ref "SV8") (pin "A3") (pinfunction "A3_A3") (pintype "passive"))
    )
    (net (code "274") (name "unconnected-(SV8-PadA4_SDA)") (class "Default")
      (node (ref "SV8") (pin "A4_SDA") (pinfunction "A4_SDA_A4_SDA") (pintype "passive"))
    )
    (net (code "275") (name "unconnected-(SV8-PadA5_SCL)") (class "Default")
      (node (ref "SV8") (pin "A5_SCL") (pinfunction "A5_SCL_A5_SCL") (pintype "passive"))
    )
    (net (code "276") (name "unconnected-(SV8-PadD0_RX)") (class "Default")
      (node (ref "SV8") (pin "D0_RX") (pinfunction "D0_RX_D0_RX") (pintype "passive"))
    )
    (net (code "277") (name "unconnected-(SV8-PadD1_TX)") (class "Default")
      (node (ref "SV8") (pin "D1_TX") (pinfunction "D1_TX_D1_TX") (pintype "passive"))
    )
    (net (code "278") (name "unconnected-(SV8-PadD4)") (class "Default")
      (node (ref "SV8") (pin "D4") (pinfunction "D4_D4") (pintype "passive"))
    )
    (net (code "279") (name "unconnected-(SV8-PadD7)") (class "Default")
      (node (ref "SV8") (pin "D7") (pinfunction "D7_D7") (pintype "passive"))
    )
    (net (code "280") (name "unconnected-(SV8-PadD8)") (class "Default")
      (node (ref "SV8") (pin "D8") (pinfunction "D8_D8") (pintype "passive"))
    )
    (net (code "281") (name "unconnected-(SV8-PadVCC)") (class "Default")
      (node (ref "SV8") (pin "VCC") (pinfunction "VCC_VCC") (pintype "passive"))
    )
    (net (code "282") (name "unconnected-(SV8-PadVSS)") (class "Default")
      (node (ref "SV8") (pin "VSS") (pinfunction "VSS_VSS") (pintype "passive"))
    )
    (net (code "283") (name "unconnected-(SW1-P1-PadA')") (class "Default")
      (node (ref "SW1") (pin "A'") (pinfunction "P1_A'") (pintype "passive"))
    )
    (net (code "284") (name "unconnected-(SW2-P1-PadA')") (class "Default")
      (node (ref "SW2") (pin "A'") (pinfunction "P1_A'") (pintype "passive"))
    )
  )
)
